# control_board.net
KiCad netlist of a schematic drawn in EAGLE
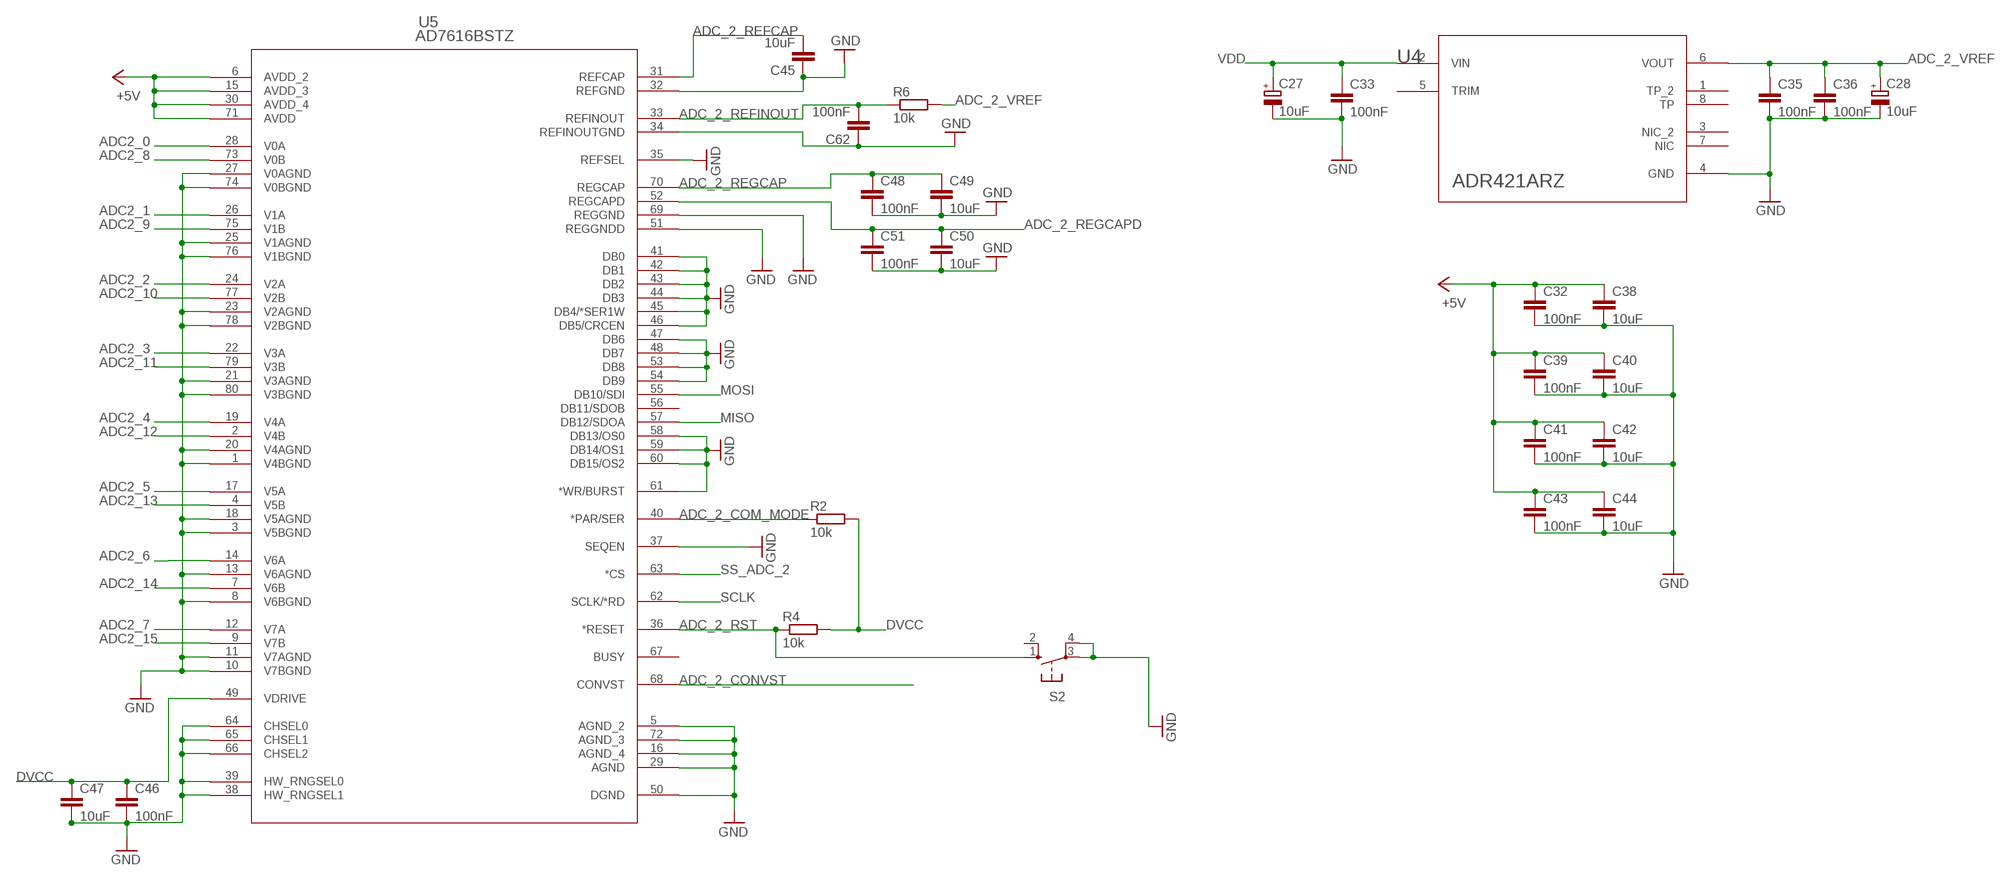
[diagram p0: schematic, sheet 1]
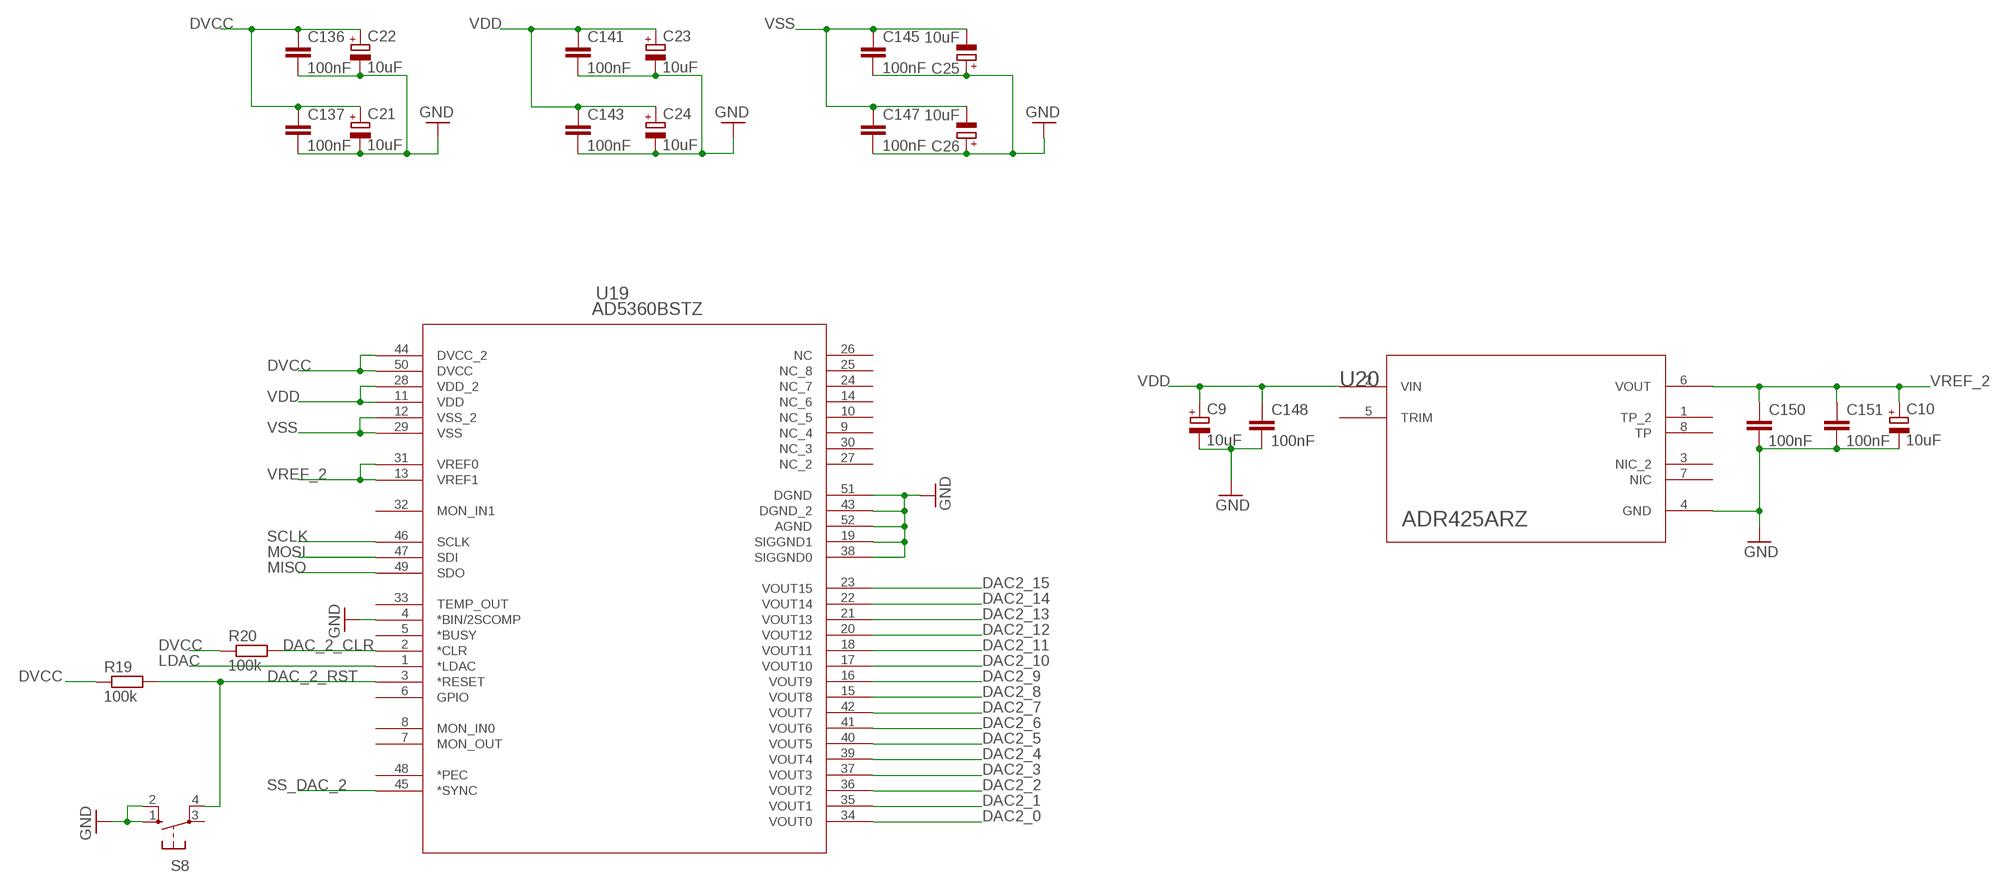
[diagram p1: schematic, sheet 2]
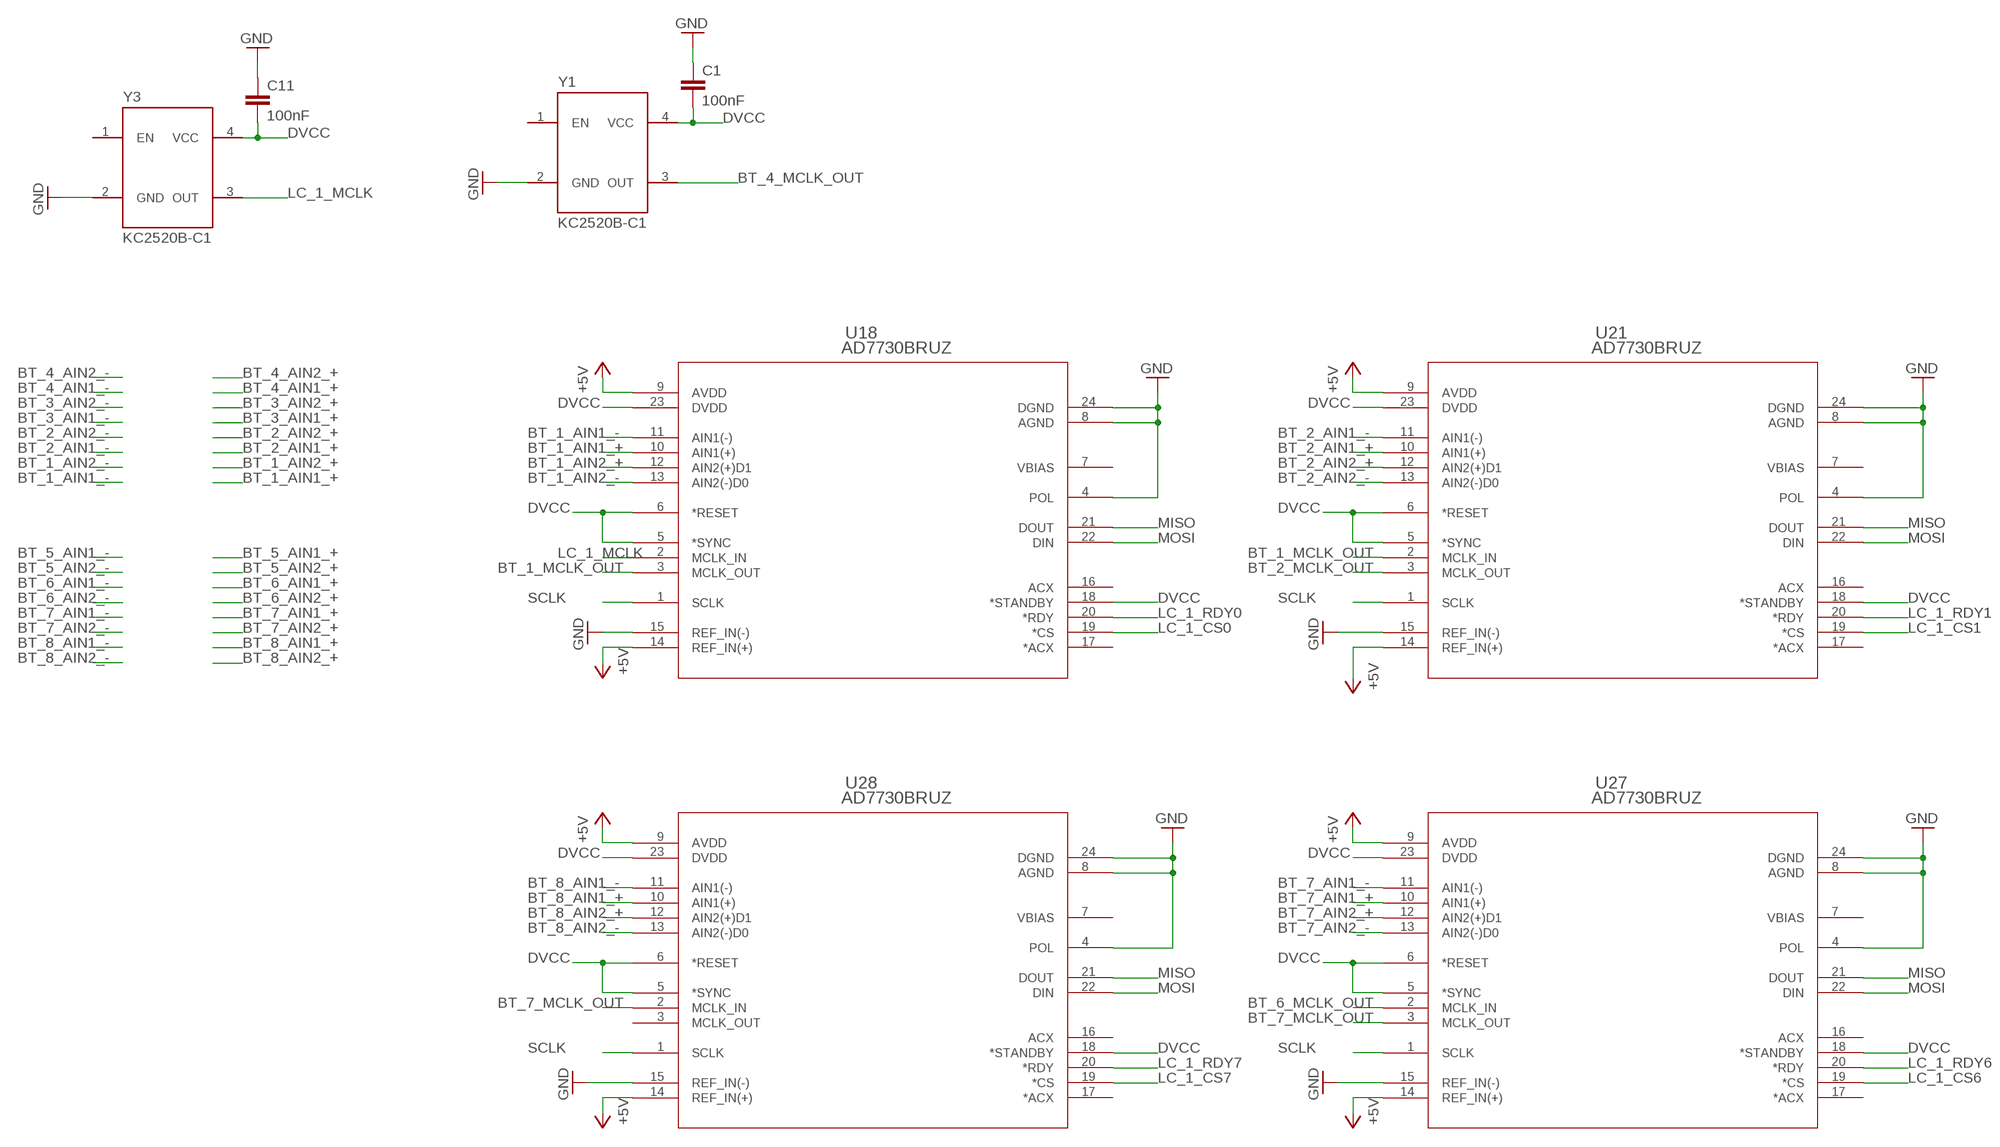
[diagram p2: schematic, sheet 3, part 1 of 2]
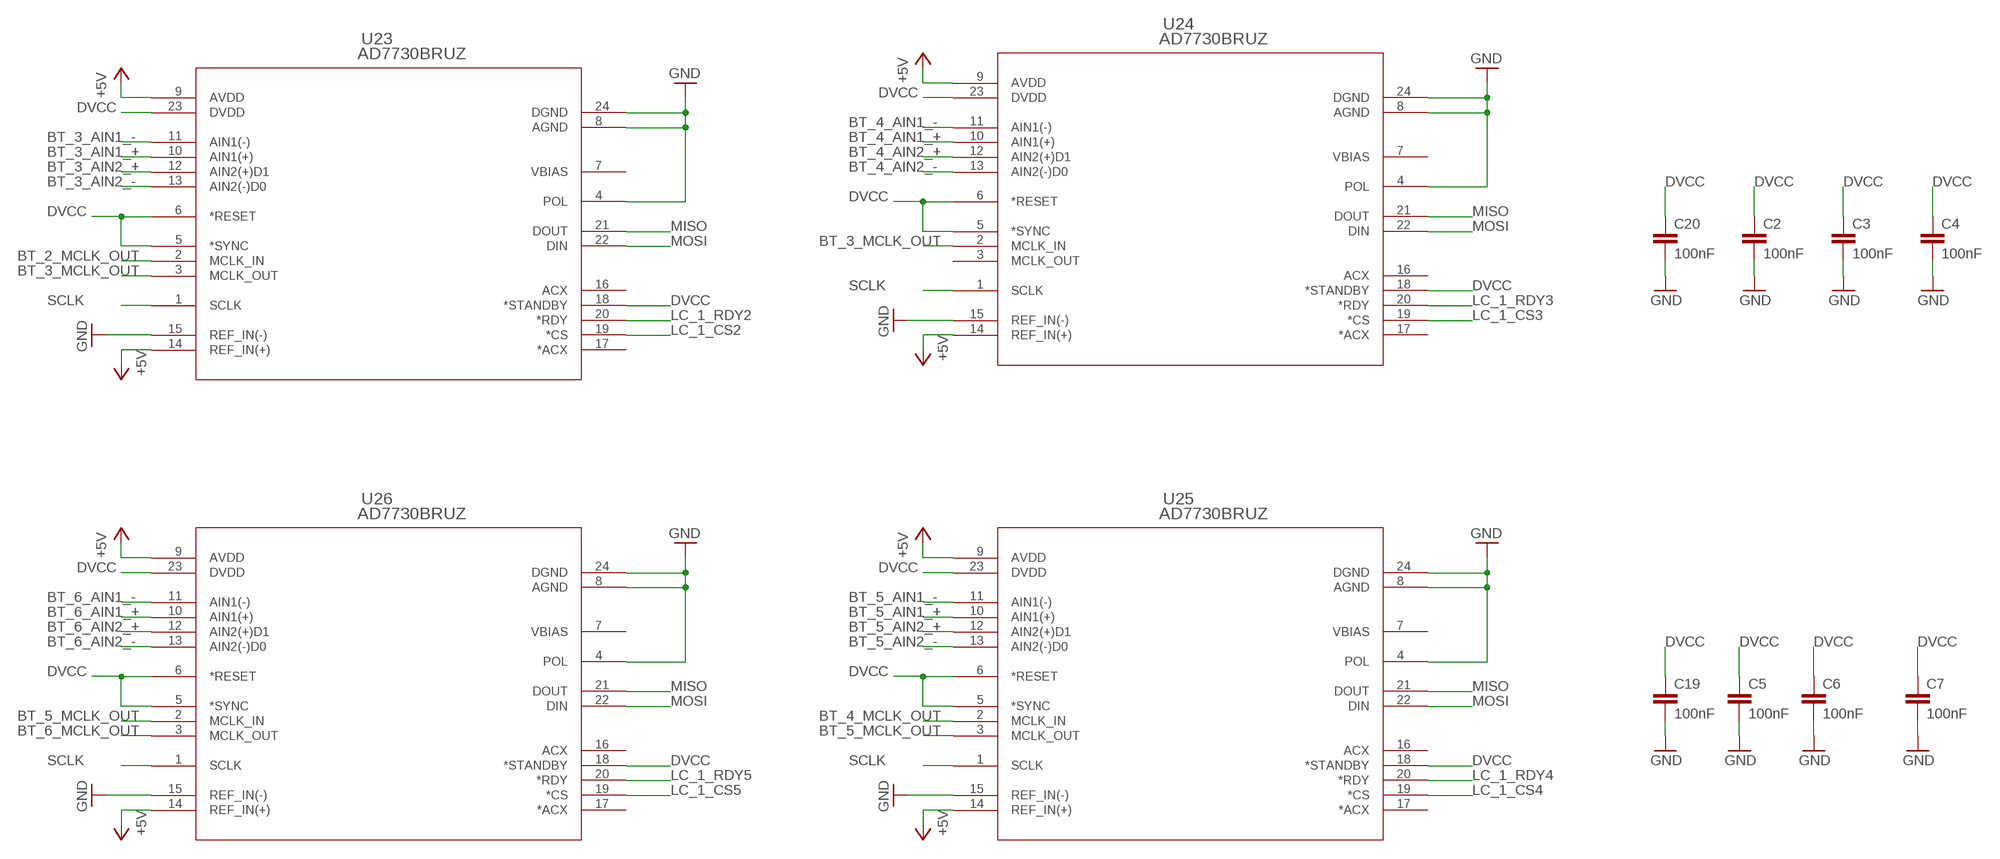
[diagram p3: schematic, sheet 3, part 2 of 2]
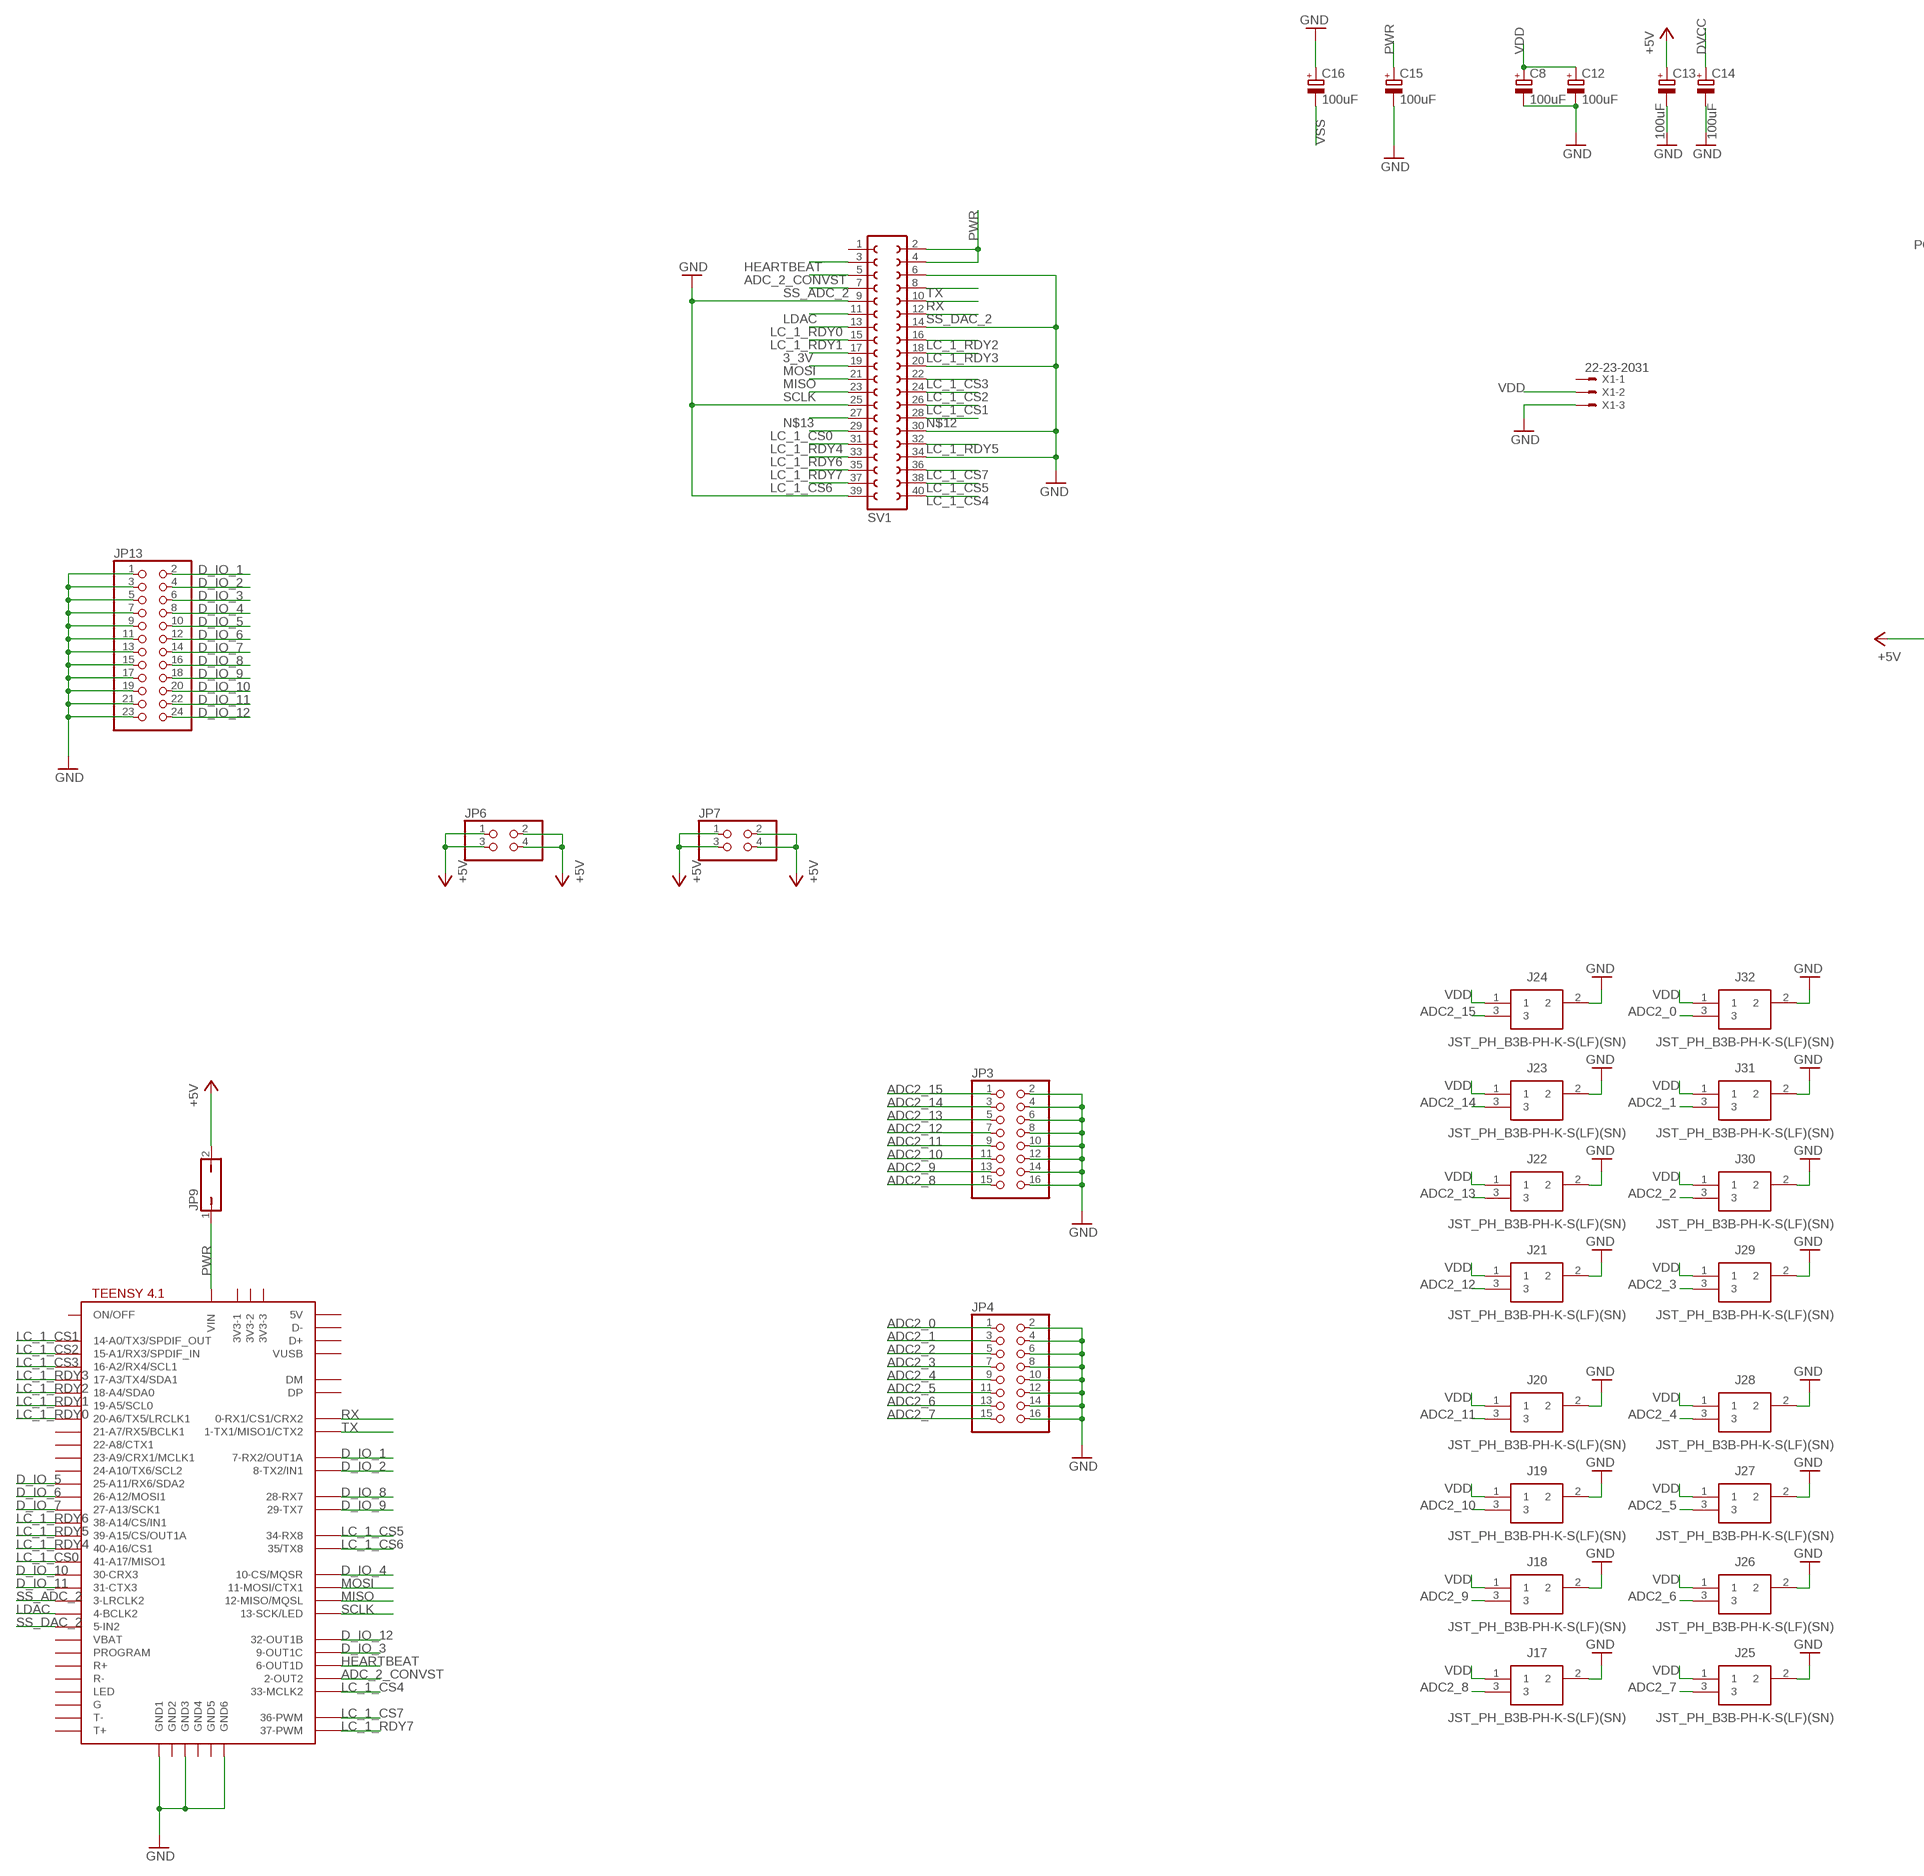
[diagram p4: schematic, sheet 4, part 1 of 2]
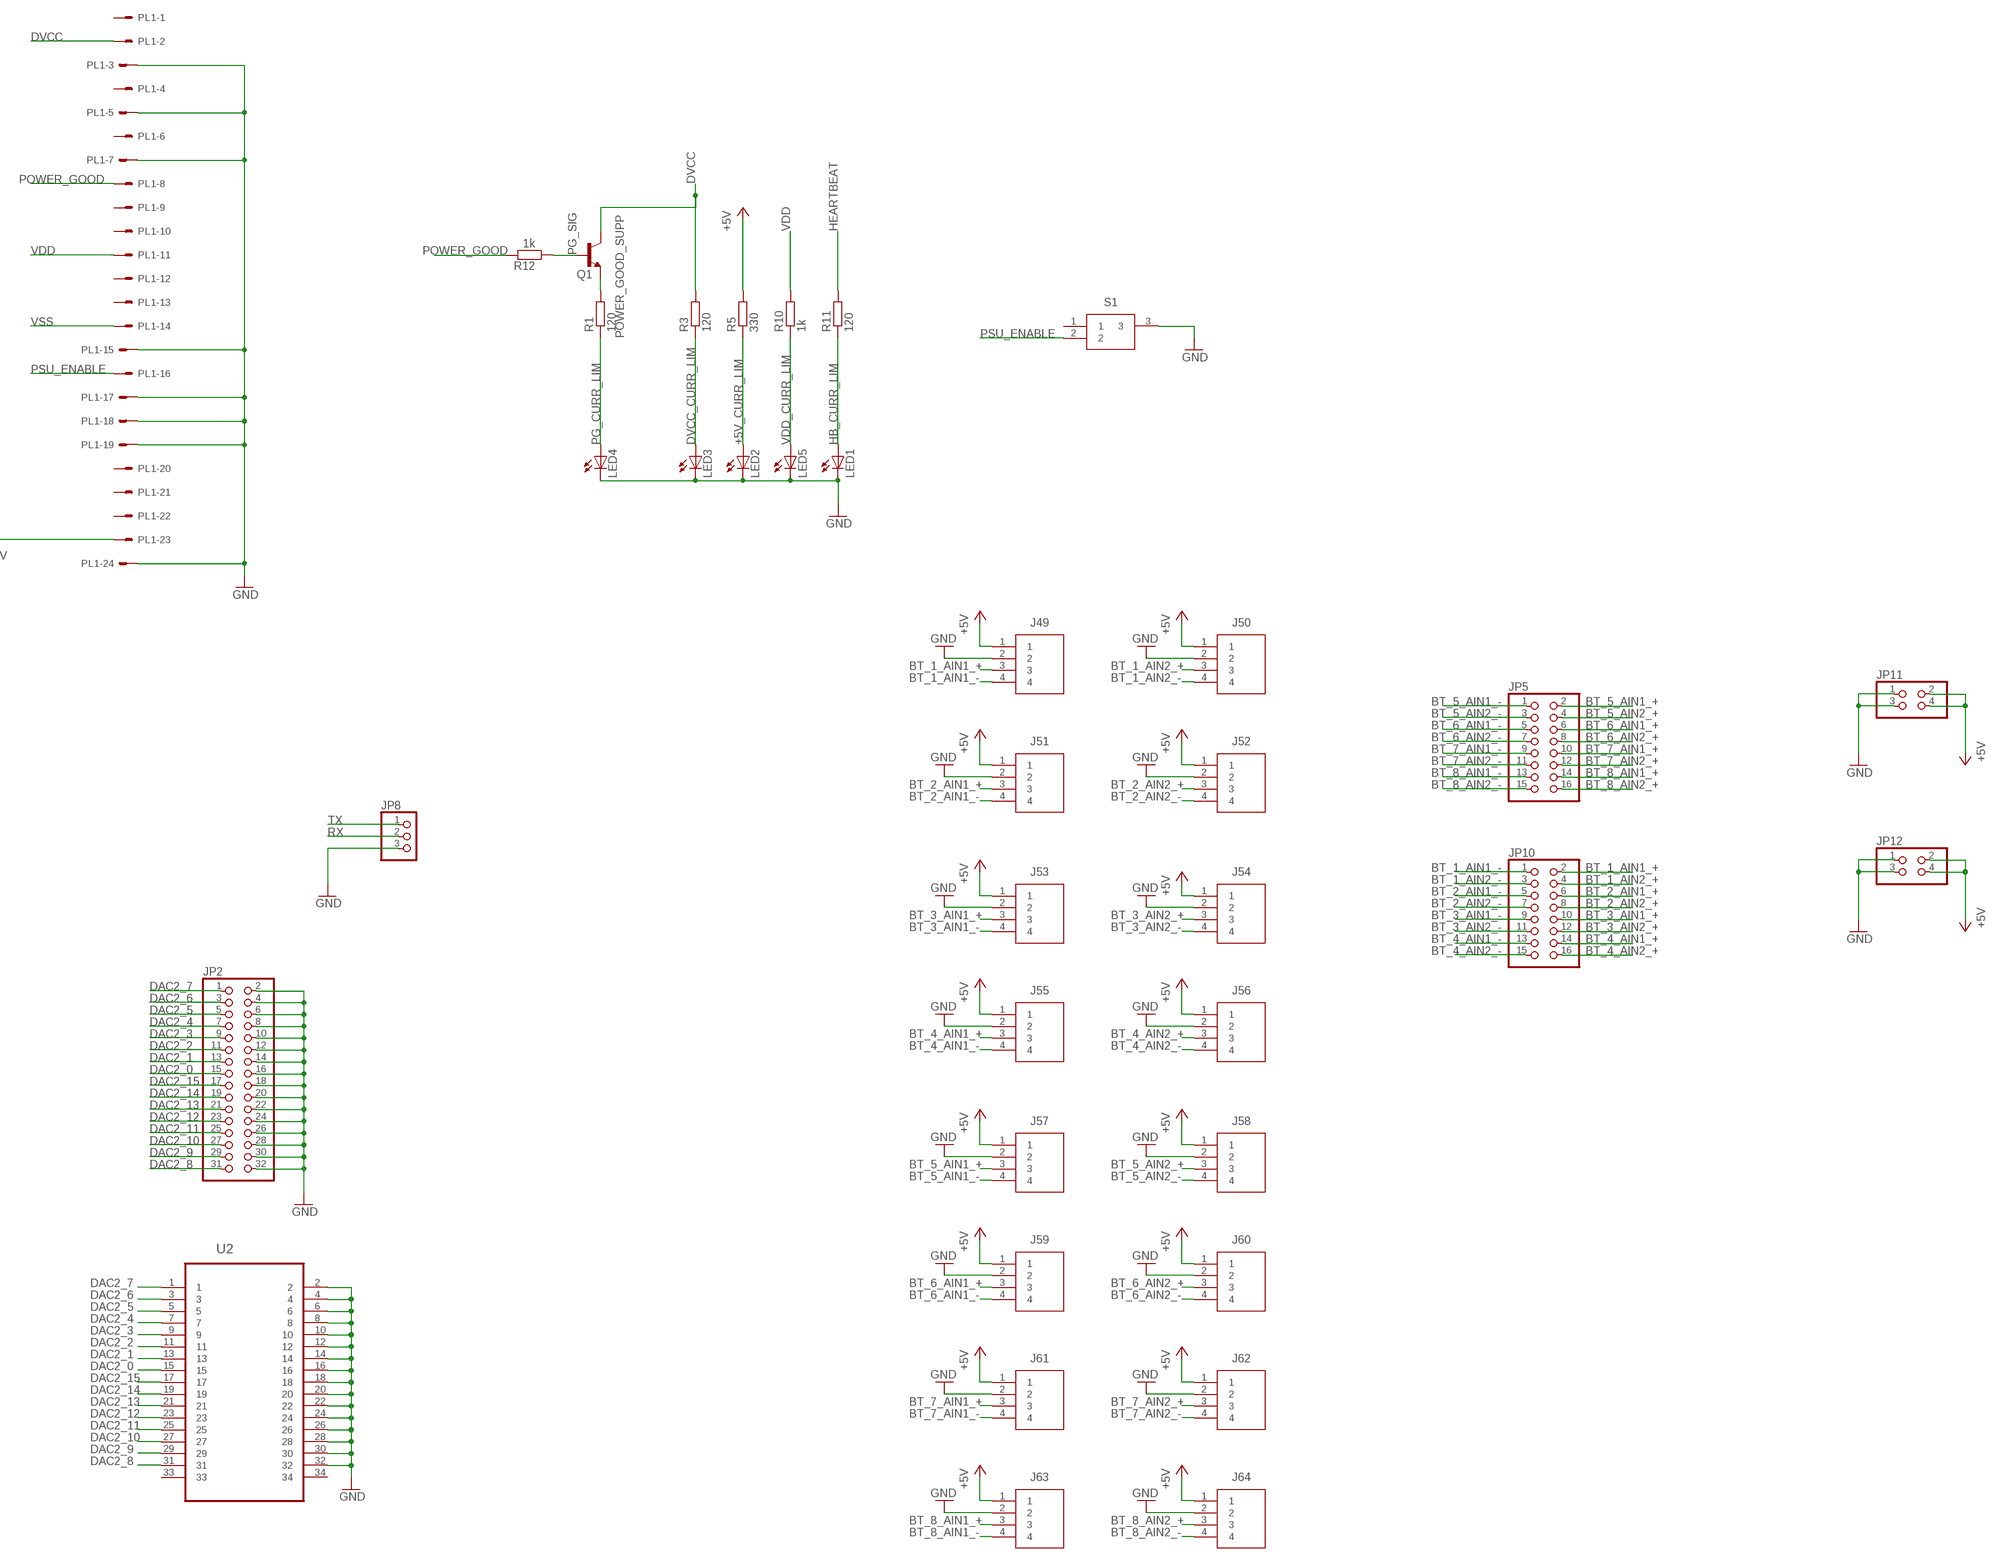
[diagram p5: schematic, sheet 4, part 2 of 2]

(export (version "E")
  (design (tool "Eeschema 10.0.6"))
  (components
    (comp (ref "C1")
      (value "100nF")
      (footprint "eagle-import:C0603")
      (libsource (lib "eagle-import") (part "C-EUC0603"))
    )
    (comp (ref "C2")
      (value "100nF")
      (footprint "eagle-import:C0603")
      (libsource (lib "eagle-import") (part "C-EUC0603"))
    )
    (comp (ref "C3")
      (value "100nF")
      (footprint "eagle-import:C0603")
      (libsource (lib "eagle-import") (part "C-EUC0603"))
    )
    (comp (ref "C4")
      (value "100nF")
      (footprint "eagle-import:C0603")
      (libsource (lib "eagle-import") (part "C-EUC0603"))
    )
    (comp (ref "C5")
      (value "100nF")
      (footprint "eagle-import:C0603")
      (libsource (lib "eagle-import") (part "C-EUC0603"))
    )
    (comp (ref "C6")
      (value "100nF")
      (footprint "eagle-import:C0603")
      (libsource (lib "eagle-import") (part "C-EUC0603"))
    )
    (comp (ref "C7")
      (value "100nF")
      (footprint "eagle-import:C0603")
      (libsource (lib "eagle-import") (part "C-EUC0603"))
    )
    (comp (ref "C11")
      (value "100nF")
      (footprint "eagle-import:C0603")
      (libsource (lib "eagle-import") (part "C-EUC0603"))
    )
    (comp (ref "C19")
      (value "100nF")
      (footprint "eagle-import:C0603")
      (libsource (lib "eagle-import") (part "C-EUC0603"))
    )
    (comp (ref "C20")
      (value "100nF")
      (footprint "eagle-import:C0603")
      (libsource (lib "eagle-import") (part "C-EUC0603"))
    )
    (comp (ref "U18")
      (value "AD7730BRUZ")
      (footprint "eagle-import:RU_24")
      (libsource (lib "eagle-import") (part "AD7730BRUZ"))
    )
    (comp (ref "U21")
      (value "AD7730BRUZ")
      (footprint "eagle-import:RU_24")
      (libsource (lib "eagle-import") (part "AD7730BRUZ"))
    )
    (comp (ref "U23")
      (value "AD7730BRUZ")
      (footprint "eagle-import:RU_24")
      (libsource (lib "eagle-import") (part "AD7730BRUZ"))
    )
    (comp (ref "U24")
      (value "AD7730BRUZ")
      (footprint "eagle-import:RU_24")
      (libsource (lib "eagle-import") (part "AD7730BRUZ"))
    )
    (comp (ref "U25")
      (value "AD7730BRUZ")
      (footprint "eagle-import:RU_24")
      (libsource (lib "eagle-import") (part "AD7730BRUZ"))
    )
    (comp (ref "U26")
      (value "AD7730BRUZ")
      (footprint "eagle-import:RU_24")
      (libsource (lib "eagle-import") (part "AD7730BRUZ"))
    )
    (comp (ref "U27")
      (value "AD7730BRUZ")
      (footprint "eagle-import:RU_24")
      (libsource (lib "eagle-import") (part "AD7730BRUZ"))
    )
    (comp (ref "U28")
      (value "AD7730BRUZ")
      (footprint "eagle-import:RU_24")
      (libsource (lib "eagle-import") (part "AD7730BRUZ"))
    )
    (comp (ref "Y1")
      (value "KC2520B-C1")
      (footprint "eagle-import:KC2520B-C1")
      (libsource (lib "eagle-import") (part "KC2520B-C1"))
    )
    (comp (ref "Y3")
      (value "KC2520B-C1")
      (footprint "eagle-import:KC2520B-C1")
      (libsource (lib "eagle-import") (part "KC2520B-C1"))
    )
    (comp (ref "C27")
      (value "10uF")
      (footprint "eagle-import:SMC_A")
      (libsource (lib "eagle-import") (part "resistor_348_CPOL-EUSMCA"))
    )
    (comp (ref "C28")
      (value "10uF")
      (footprint "eagle-import:SMC_A")
      (libsource (lib "eagle-import") (part "resistor_348_CPOL-EUSMCA"))
    )
    (comp (ref "C32")
      (value "100nF")
      (footprint "eagle-import:C0603")
      (libsource (lib "eagle-import") (part "C-EUC0603"))
    )
    (comp (ref "C33")
      (value "100nF")
      (footprint "eagle-import:C0603")
      (libsource (lib "eagle-import") (part "C-EUC0603"))
    )
    (comp (ref "C35")
      (value "100nF")
      (footprint "eagle-import:C0603")
      (libsource (lib "eagle-import") (part "C-EUC0603"))
    )
    (comp (ref "C36")
      (value "100nF")
      (footprint "eagle-import:C0603")
      (libsource (lib "eagle-import") (part "C-EUC0603"))
    )
    (comp (ref "C38")
      (value "10uF")
      (footprint "eagle-import:C0603")
      (libsource (lib "eagle-import") (part "C-EUC0603"))
    )
    (comp (ref "C39")
      (value "100nF")
      (footprint "eagle-import:C0603")
      (libsource (lib "eagle-import") (part "C-EUC0603"))
    )
    (comp (ref "C40")
      (value "10uF")
      (footprint "eagle-import:C0603")
      (libsource (lib "eagle-import") (part "C-EUC0603"))
    )
    (comp (ref "C41")
      (value "100nF")
      (footprint "eagle-import:C0603")
      (libsource (lib "eagle-import") (part "C-EUC0603"))
    )
    (comp (ref "C42")
      (value "10uF")
      (footprint "eagle-import:C0603")
      (libsource (lib "eagle-import") (part "C-EUC0603"))
    )
    (comp (ref "C43")
      (value "100nF")
      (footprint "eagle-import:C0603")
      (libsource (lib "eagle-import") (part "C-EUC0603"))
    )
    (comp (ref "C44")
      (value "10uF")
      (footprint "eagle-import:C0603")
      (libsource (lib "eagle-import") (part "C-EUC0603"))
    )
    (comp (ref "C45")
      (value "10uF")
      (footprint "eagle-import:C0603")
      (libsource (lib "eagle-import") (part "C-EUC0603"))
    )
    (comp (ref "C46")
      (value "100nF")
      (footprint "eagle-import:C0603")
      (libsource (lib "eagle-import") (part "C-EUC0603"))
    )
    (comp (ref "C47")
      (value "10uF")
      (footprint "eagle-import:C0603")
      (libsource (lib "eagle-import") (part "C-EUC0603"))
    )
    (comp (ref "C48")
      (value "100nF")
      (footprint "eagle-import:C0603")
      (libsource (lib "eagle-import") (part "C-EUC0603"))
    )
    (comp (ref "C49")
      (value "10uF")
      (footprint "eagle-import:C0603")
      (libsource (lib "eagle-import") (part "C-EUC0603"))
    )
    (comp (ref "C50")
      (value "10uF")
      (footprint "eagle-import:C0603")
      (libsource (lib "eagle-import") (part "C-EUC0603"))
    )
    (comp (ref "C51")
      (value "100nF")
      (footprint "eagle-import:C0603")
      (libsource (lib "eagle-import") (part "C-EUC0603"))
    )
    (comp (ref "C62")
      (value "100nF")
      (footprint "eagle-import:C0603")
      (libsource (lib "eagle-import") (part "C-EUC0603"))
    )
    (comp (ref "R2")
      (value "10k")
      (footprint "eagle-import:R0603")
      (libsource (lib "eagle-import") (part "R-EU_R0603"))
    )
    (comp (ref "R4")
      (value "10k")
      (footprint "eagle-import:R0603")
      (libsource (lib "eagle-import") (part "R-EU_R0603"))
    )
    (comp (ref "R6")
      (value "10k")
      (footprint "eagle-import:R0603")
      (libsource (lib "eagle-import") (part "R-EU_R0603"))
    )
    (comp (ref "S2")
      (value "10-XX")
      (footprint "eagle-import:B3F-10XX")
      (fields (field (name "MPN") "B3F-1000"))
      (libsource (lib "eagle-import") (part "10-XX"))
    )
    (comp (ref "U4")
      (value "ADR421ARZ")
      (footprint "eagle-import:R_8")
      (fields (field (name "MANUFACTURER_PART_NUMBER") "ADR423ARZ"))
      (libsource (lib "eagle-import") (part "ADR423ARZ"))
    )
    (comp (ref "U5")
      (value "AD7616BSTZ")
      (footprint "eagle-import:ST_80_2")
      (libsource (lib "eagle-import") (part "AD7616BSTZ"))
    )
    (comp (ref "C9")
      (value "10uF")
      (footprint "eagle-import:SMC_A")
      (libsource (lib "eagle-import") (part "resistor_348_CPOL-EUSMCA"))
    )
    (comp (ref "C10")
      (value "10uF")
      (footprint "eagle-import:SMC_A")
      (libsource (lib "eagle-import") (part "resistor_348_CPOL-EUSMCA"))
    )
    (comp (ref "C21")
      (value "10uF")
      (footprint "eagle-import:SMC_A")
      (libsource (lib "eagle-import") (part "resistor_348_CPOL-EUSMCA"))
    )
    (comp (ref "C22")
      (value "10uF")
      (footprint "eagle-import:SMC_A")
      (libsource (lib "eagle-import") (part "resistor_348_CPOL-EUSMCA"))
    )
    (comp (ref "C23")
      (value "10uF")
      (footprint "eagle-import:SMC_A")
      (libsource (lib "eagle-import") (part "resistor_348_CPOL-EUSMCA"))
    )
    (comp (ref "C24")
      (value "10uF")
      (footprint "eagle-import:SMC_A")
      (libsource (lib "eagle-import") (part "resistor_348_CPOL-EUSMCA"))
    )
    (comp (ref "C25")
      (value "10uF")
      (footprint "eagle-import:SMC_A")
      (libsource (lib "eagle-import") (part "resistor_348_CPOL-EUSMCA"))
    )
    (comp (ref "C26")
      (value "10uF")
      (footprint "eagle-import:SMC_A")
      (libsource (lib "eagle-import") (part "resistor_348_CPOL-EUSMCA"))
    )
    (comp (ref "C136")
      (value "100nF")
      (footprint "eagle-import:C0603")
      (libsource (lib "eagle-import") (part "C-EUC0603"))
    )
    (comp (ref "C137")
      (value "100nF")
      (footprint "eagle-import:C0603")
      (libsource (lib "eagle-import") (part "C-EUC0603"))
    )
    (comp (ref "C141")
      (value "100nF")
      (footprint "eagle-import:C0603")
      (libsource (lib "eagle-import") (part "C-EUC0603"))
    )
    (comp (ref "C143")
      (value "100nF")
      (footprint "eagle-import:C0603")
      (libsource (lib "eagle-import") (part "C-EUC0603"))
    )
    (comp (ref "C145")
      (value "100nF")
      (footprint "eagle-import:C0603")
      (libsource (lib "eagle-import") (part "C-EUC0603"))
    )
    (comp (ref "C147")
      (value "100nF")
      (footprint "eagle-import:C0603")
      (libsource (lib "eagle-import") (part "C-EUC0603"))
    )
    (comp (ref "C148")
      (value "100nF")
      (footprint "eagle-import:C0603")
      (libsource (lib "eagle-import") (part "C-EUC0603"))
    )
    (comp (ref "C150")
      (value "100nF")
      (footprint "eagle-import:C0603")
      (libsource (lib "eagle-import") (part "C-EUC0603"))
    )
    (comp (ref "C151")
      (value "100nF")
      (footprint "eagle-import:C0603")
      (libsource (lib "eagle-import") (part "C-EUC0603"))
    )
    (comp (ref "R19")
      (value "100k")
      (footprint "eagle-import:R0603")
      (libsource (lib "eagle-import") (part "R-EU_R0603"))
    )
    (comp (ref "R20")
      (value "100k")
      (footprint "eagle-import:R0603")
      (libsource (lib "eagle-import") (part "R-EU_R0603"))
    )
    (comp (ref "S8")
      (value "10-XX")
      (footprint "eagle-import:B3F-10XX")
      (fields (field (name "MPN") "B3F-1000"))
      (libsource (lib "eagle-import") (part "10-XX"))
    )
    (comp (ref "U19")
      (value "AD5360BSTZ")
      (footprint "eagle-import:ST_52")
      (libsource (lib "eagle-import") (part "AD5360BSTZ"))
    )
    (comp (ref "U20")
      (value "ADR425ARZ")
      (footprint "eagle-import:R_8")
      (fields (field (name "MANUFACTURER_PART_NUMBER") "ADR423ARZ"))
      (libsource (lib "eagle-import") (part "ADR423ARZ"))
    )
    (comp (ref "C8")
      (value "100uF")
      (footprint "eagle-import:E3,5-8")
      (libsource (lib "eagle-import") (part "CPOL-EUE3.5-8"))
    )
    (comp (ref "C12")
      (value "100uF")
      (footprint "eagle-import:E3,5-8")
      (libsource (lib "eagle-import") (part "CPOL-EUE3.5-8"))
    )
    (comp (ref "C13")
      (value "100uF")
      (footprint "eagle-import:E3,5-8")
      (libsource (lib "eagle-import") (part "CPOL-EUE3.5-8"))
    )
    (comp (ref "C14")
      (value "100uF")
      (footprint "eagle-import:E3,5-8")
      (libsource (lib "eagle-import") (part "CPOL-EUE3.5-8"))
    )
    (comp (ref "C15")
      (value "100uF")
      (footprint "eagle-import:E3,5-8")
      (libsource (lib "eagle-import") (part "CPOL-EUE3.5-8"))
    )
    (comp (ref "C16")
      (value "100uF")
      (footprint "eagle-import:E3,5-8")
      (libsource (lib "eagle-import") (part "CPOL-EUE3.5-8"))
    )
    (comp (ref "J17")
      (value "JST_PH_B3B-PH-K-S(LF)(SN)")
      (footprint "eagle-import:JST_PH_SHDR3W50P0X200_1X3_790X450X600")
      (fields
        (field (name "MANUFACTURER_PART_NUMBER") "B3B-PH-K-S(LF)(SN)")
        (field (name "RS_PART_NUMBER") "8201431P")
      )
      (libsource (lib "eagle-import") (part "JST_PH_B3B-PH-K-S(LF)(SN)"))
    )
    (comp (ref "J18")
      (value "JST_PH_B3B-PH-K-S(LF)(SN)")
      (footprint "eagle-import:JST_PH_SHDR3W50P0X200_1X3_790X450X600")
      (fields
        (field (name "MANUFACTURER_PART_NUMBER") "B3B-PH-K-S(LF)(SN)")
        (field (name "RS_PART_NUMBER") "8201431P")
      )
      (libsource (lib "eagle-import") (part "JST_PH_B3B-PH-K-S(LF)(SN)"))
    )
    (comp (ref "J19")
      (value "JST_PH_B3B-PH-K-S(LF)(SN)")
      (footprint "eagle-import:JST_PH_SHDR3W50P0X200_1X3_790X450X600")
      (fields
        (field (name "MANUFACTURER_PART_NUMBER") "B3B-PH-K-S(LF)(SN)")
        (field (name "RS_PART_NUMBER") "8201431P")
      )
      (libsource (lib "eagle-import") (part "JST_PH_B3B-PH-K-S(LF)(SN)"))
    )
    (comp (ref "J20")
      (value "JST_PH_B3B-PH-K-S(LF)(SN)")
      (footprint "eagle-import:JST_PH_SHDR3W50P0X200_1X3_790X450X600")
      (fields
        (field (name "MANUFACTURER_PART_NUMBER") "B3B-PH-K-S(LF)(SN)")
        (field (name "RS_PART_NUMBER") "8201431P")
      )
      (libsource (lib "eagle-import") (part "JST_PH_B3B-PH-K-S(LF)(SN)"))
    )
    (comp (ref "J21")
      (value "JST_PH_B3B-PH-K-S(LF)(SN)")
      (footprint "eagle-import:JST_PH_SHDR3W50P0X200_1X3_790X450X600")
      (fields
        (field (name "MANUFACTURER_PART_NUMBER") "B3B-PH-K-S(LF)(SN)")
        (field (name "RS_PART_NUMBER") "8201431P")
      )
      (libsource (lib "eagle-import") (part "JST_PH_B3B-PH-K-S(LF)(SN)"))
    )
    (comp (ref "J22")
      (value "JST_PH_B3B-PH-K-S(LF)(SN)")
      (footprint "eagle-import:JST_PH_SHDR3W50P0X200_1X3_790X450X600")
      (fields
        (field (name "MANUFACTURER_PART_NUMBER") "B3B-PH-K-S(LF)(SN)")
        (field (name "RS_PART_NUMBER") "8201431P")
      )
      (libsource (lib "eagle-import") (part "JST_PH_B3B-PH-K-S(LF)(SN)"))
    )
    (comp (ref "J23")
      (value "JST_PH_B3B-PH-K-S(LF)(SN)")
      (footprint "eagle-import:JST_PH_SHDR3W50P0X200_1X3_790X450X600")
      (fields
        (field (name "MANUFACTURER_PART_NUMBER") "B3B-PH-K-S(LF)(SN)")
        (field (name "RS_PART_NUMBER") "8201431P")
      )
      (libsource (lib "eagle-import") (part "JST_PH_B3B-PH-K-S(LF)(SN)"))
    )
    (comp (ref "J24")
      (value "JST_PH_B3B-PH-K-S(LF)(SN)")
      (footprint "eagle-import:JST_PH_SHDR3W50P0X200_1X3_790X450X600")
      (fields
        (field (name "MANUFACTURER_PART_NUMBER") "B3B-PH-K-S(LF)(SN)")
        (field (name "RS_PART_NUMBER") "8201431P")
      )
      (libsource (lib "eagle-import") (part "JST_PH_B3B-PH-K-S(LF)(SN)"))
    )
    (comp (ref "J25")
      (value "JST_PH_B3B-PH-K-S(LF)(SN)")
      (footprint "eagle-import:JST_PH_SHDR3W50P0X200_1X3_790X450X600")
      (fields
        (field (name "MANUFACTURER_PART_NUMBER") "B3B-PH-K-S(LF)(SN)")
        (field (name "RS_PART_NUMBER") "8201431P")
      )
      (libsource (lib "eagle-import") (part "JST_PH_B3B-PH-K-S(LF)(SN)"))
    )
    (comp (ref "J26")
      (value "JST_PH_B3B-PH-K-S(LF)(SN)")
      (footprint "eagle-import:JST_PH_SHDR3W50P0X200_1X3_790X450X600")
      (fields
        (field (name "MANUFACTURER_PART_NUMBER") "B3B-PH-K-S(LF)(SN)")
        (field (name "RS_PART_NUMBER") "8201431P")
      )
      (libsource (lib "eagle-import") (part "JST_PH_B3B-PH-K-S(LF)(SN)"))
    )
    (comp (ref "J27")
      (value "JST_PH_B3B-PH-K-S(LF)(SN)")
      (footprint "eagle-import:JST_PH_SHDR3W50P0X200_1X3_790X450X600")
      (fields
        (field (name "MANUFACTURER_PART_NUMBER") "B3B-PH-K-S(LF)(SN)")
        (field (name "RS_PART_NUMBER") "8201431P")
      )
      (libsource (lib "eagle-import") (part "JST_PH_B3B-PH-K-S(LF)(SN)"))
    )
    (comp (ref "J28")
      (value "JST_PH_B3B-PH-K-S(LF)(SN)")
      (footprint "eagle-import:JST_PH_SHDR3W50P0X200_1X3_790X450X600")
      (fields
        (field (name "MANUFACTURER_PART_NUMBER") "B3B-PH-K-S(LF)(SN)")
        (field (name "RS_PART_NUMBER") "8201431P")
      )
      (libsource (lib "eagle-import") (part "JST_PH_B3B-PH-K-S(LF)(SN)"))
    )
    (comp (ref "J29")
      (value "JST_PH_B3B-PH-K-S(LF)(SN)")
      (footprint "eagle-import:JST_PH_SHDR3W50P0X200_1X3_790X450X600")
      (fields
        (field (name "MANUFACTURER_PART_NUMBER") "B3B-PH-K-S(LF)(SN)")
        (field (name "RS_PART_NUMBER") "8201431P")
      )
      (libsource (lib "eagle-import") (part "JST_PH_B3B-PH-K-S(LF)(SN)"))
    )
    (comp (ref "J30")
      (value "JST_PH_B3B-PH-K-S(LF)(SN)")
      (footprint "eagle-import:JST_PH_SHDR3W50P0X200_1X3_790X450X600")
      (fields
        (field (name "MANUFACTURER_PART_NUMBER") "B3B-PH-K-S(LF)(SN)")
        (field (name "RS_PART_NUMBER") "8201431P")
      )
      (libsource (lib "eagle-import") (part "JST_PH_B3B-PH-K-S(LF)(SN)"))
    )
    (comp (ref "J31")
      (value "JST_PH_B3B-PH-K-S(LF)(SN)")
      (footprint "eagle-import:JST_PH_SHDR3W50P0X200_1X3_790X450X600")
      (fields
        (field (name "MANUFACTURER_PART_NUMBER") "B3B-PH-K-S(LF)(SN)")
        (field (name "RS_PART_NUMBER") "8201431P")
      )
      (libsource (lib "eagle-import") (part "JST_PH_B3B-PH-K-S(LF)(SN)"))
    )
    (comp (ref "J32")
      (value "JST_PH_B3B-PH-K-S(LF)(SN)")
      (footprint "eagle-import:JST_PH_SHDR3W50P0X200_1X3_790X450X600")
      (fields
        (field (name "MANUFACTURER_PART_NUMBER") "B3B-PH-K-S(LF)(SN)")
        (field (name "RS_PART_NUMBER") "8201431P")
      )
      (libsource (lib "eagle-import") (part "JST_PH_B3B-PH-K-S(LF)(SN)"))
    )
    (comp (ref "J49")
      (value "B4B-PH-K-S(LF)(SN)")
      (footprint "eagle-import:SHDR4W50P0X200_1X4_990X450X600")
      (fields (field (name "RS_PART_NUMBER") "8201434P"))
      (libsource (lib "eagle-import") (part "B4B-PH-K-S(LF)(SN)"))
    )
    (comp (ref "J50")
      (value "B4B-PH-K-S(LF)(SN)")
      (footprint "eagle-import:SHDR4W50P0X200_1X4_990X450X600")
      (fields (field (name "RS_PART_NUMBER") "8201434P"))
      (libsource (lib "eagle-import") (part "B4B-PH-K-S(LF)(SN)"))
    )
    (comp (ref "J51")
      (value "B4B-PH-K-S(LF)(SN)")
      (footprint "eagle-import:SHDR4W50P0X200_1X4_990X450X600")
      (fields (field (name "RS_PART_NUMBER") "8201434P"))
      (libsource (lib "eagle-import") (part "B4B-PH-K-S(LF)(SN)"))
    )
    (comp (ref "J52")
      (value "B4B-PH-K-S(LF)(SN)")
      (footprint "eagle-import:SHDR4W50P0X200_1X4_990X450X600")
      (fields (field (name "RS_PART_NUMBER") "8201434P"))
      (libsource (lib "eagle-import") (part "B4B-PH-K-S(LF)(SN)"))
    )
    (comp (ref "J53")
      (value "B4B-PH-K-S(LF)(SN)")
      (footprint "eagle-import:SHDR4W50P0X200_1X4_990X450X600")
      (fields (field (name "RS_PART_NUMBER") "8201434P"))
      (libsource (lib "eagle-import") (part "B4B-PH-K-S(LF)(SN)"))
    )
    (comp (ref "J54")
      (value "B4B-PH-K-S(LF)(SN)")
      (footprint "eagle-import:SHDR4W50P0X200_1X4_990X450X600")
      (fields (field (name "RS_PART_NUMBER") "8201434P"))
      (libsource (lib "eagle-import") (part "B4B-PH-K-S(LF)(SN)"))
    )
    (comp (ref "J55")
      (value "B4B-PH-K-S(LF)(SN)")
      (footprint "eagle-import:SHDR4W50P0X200_1X4_990X450X600")
      (fields (field (name "RS_PART_NUMBER") "8201434P"))
      (libsource (lib "eagle-import") (part "B4B-PH-K-S(LF)(SN)"))
    )
    (comp (ref "J56")
      (value "B4B-PH-K-S(LF)(SN)")
      (footprint "eagle-import:SHDR4W50P0X200_1X4_990X450X600")
      (fields (field (name "RS_PART_NUMBER") "8201434P"))
      (libsource (lib "eagle-import") (part "B4B-PH-K-S(LF)(SN)"))
    )
    (comp (ref "J57")
      (value "B4B-PH-K-S(LF)(SN)")
      (footprint "eagle-import:SHDR4W50P0X200_1X4_990X450X600")
      (fields (field (name "RS_PART_NUMBER") "8201434P"))
      (libsource (lib "eagle-import") (part "B4B-PH-K-S(LF)(SN)"))
    )
    (comp (ref "J58")
      (value "B4B-PH-K-S(LF)(SN)")
      (footprint "eagle-import:SHDR4W50P0X200_1X4_990X450X600")
      (fields (field (name "RS_PART_NUMBER") "8201434P"))
      (libsource (lib "eagle-import") (part "B4B-PH-K-S(LF)(SN)"))
    )
    (comp (ref "J59")
      (value "B4B-PH-K-S(LF)(SN)")
      (footprint "eagle-import:SHDR4W50P0X200_1X4_990X450X600")
      (fields (field (name "RS_PART_NUMBER") "8201434P"))
      (libsource (lib "eagle-import") (part "B4B-PH-K-S(LF)(SN)"))
    )
    (comp (ref "J60")
      (value "B4B-PH-K-S(LF)(SN)")
      (footprint "eagle-import:SHDR4W50P0X200_1X4_990X450X600")
      (fields (field (name "RS_PART_NUMBER") "8201434P"))
      (libsource (lib "eagle-import") (part "B4B-PH-K-S(LF)(SN)"))
    )
    (comp (ref "J61")
      (value "B4B-PH-K-S(LF)(SN)")
      (footprint "eagle-import:SHDR4W50P0X200_1X4_990X450X600")
      (fields (field (name "RS_PART_NUMBER") "8201434P"))
      (libsource (lib "eagle-import") (part "B4B-PH-K-S(LF)(SN)"))
    )
    (comp (ref "J62")
      (value "B4B-PH-K-S(LF)(SN)")
      (footprint "eagle-import:SHDR4W50P0X200_1X4_990X450X600")
      (fields (field (name "RS_PART_NUMBER") "8201434P"))
      (libsource (lib "eagle-import") (part "B4B-PH-K-S(LF)(SN)"))
    )
    (comp (ref "J63")
      (value "B4B-PH-K-S(LF)(SN)")
      (footprint "eagle-import:SHDR4W50P0X200_1X4_990X450X600")
      (fields (field (name "RS_PART_NUMBER") "8201434P"))
      (libsource (lib "eagle-import") (part "B4B-PH-K-S(LF)(SN)"))
    )
    (comp (ref "J64")
      (value "B4B-PH-K-S(LF)(SN)")
      (footprint "eagle-import:SHDR4W50P0X200_1X4_990X450X600")
      (fields (field (name "RS_PART_NUMBER") "8201434P"))
      (libsource (lib "eagle-import") (part "B4B-PH-K-S(LF)(SN)"))
    )
    (comp (ref "JP2")
      (value "PINHD-2X16/90")
      (footprint "eagle-import:2X16_90")
      (libsource (lib "eagle-import") (part "PINHD-2X16/90"))
    )
    (comp (ref "JP3")
      (value "PINHD-2X8/90")
      (footprint "eagle-import:2X08_90")
      (libsource (lib "eagle-import") (part "PINHD-2X8/90"))
    )
    (comp (ref "JP4")
      (value "PINHD-2X8/90")
      (footprint "eagle-import:2X08_90")
      (libsource (lib "eagle-import") (part "PINHD-2X8/90"))
    )
    (comp (ref "JP5")
      (value "PINHD-2X8")
      (footprint "eagle-import:2X08")
      (libsource (lib "eagle-import") (part "PINHD-2X8"))
    )
    (comp (ref "JP6")
      (value "PINHD-2X2/90")
      (footprint "eagle-import:2X02_90")
      (libsource (lib "eagle-import") (part "PINHD-2X2/90"))
    )
    (comp (ref "JP7")
      (value "PINHD-2X2/90")
      (footprint "eagle-import:2X02_90")
      (libsource (lib "eagle-import") (part "PINHD-2X2/90"))
    )
    (comp (ref "JP8")
      (value "PINHD-1X3")
      (footprint "eagle-import:1X03")
      (libsource (lib "eagle-import") (part "PINHD-1X3"))
    )
    (comp (ref "JP9")
      (value "JP1Q")
      (footprint "eagle-import:JP1")
      (libsource (lib "eagle-import") (part "JP1Q"))
    )
    (comp (ref "JP10")
      (value "PINHD-2X8")
      (footprint "eagle-import:2X08")
      (libsource (lib "eagle-import") (part "PINHD-2X8"))
    )
    (comp (ref "JP11")
      (value "PINHD-2X2")
      (footprint "eagle-import:2X02")
      (libsource (lib "eagle-import") (part "PINHD-2X2"))
    )
    (comp (ref "JP12")
      (value "PINHD-2X2")
      (footprint "eagle-import:2X02")
      (libsource (lib "eagle-import") (part "PINHD-2X2"))
    )
    (comp (ref "JP13")
      (value "PINHD-2X12_2.54-SMD")
      (footprint "eagle-import:2X12SMD")
      (libsource (lib "eagle-import") (part "PINHD-2X12_2.54-SMD"))
    )
    (comp (ref "LED1")
      (value "LEDCHIP-LED0603")
      (footprint "eagle-import:CHIP-LED0603")
      (libsource (lib "eagle-import") (part "LEDCHIP-LED0603"))
    )
    (comp (ref "LED2")
      (value "LEDCHIP-LED0603")
      (footprint "eagle-import:CHIP-LED0603")
      (libsource (lib "eagle-import") (part "LEDCHIP-LED0603"))
    )
    (comp (ref "LED3")
      (value "LEDCHIP-LED0603")
      (footprint "eagle-import:CHIP-LED0603")
      (libsource (lib "eagle-import") (part "LEDCHIP-LED0603"))
    )
    (comp (ref "LED4")
      (value "LEDCHIP-LED0603")
      (footprint "eagle-import:CHIP-LED0603")
      (libsource (lib "eagle-import") (part "LEDCHIP-LED0603"))
    )
    (comp (ref "LED5")
      (value "LEDCHIP-LED0603")
      (footprint "eagle-import:CHIP-LED0603")
      (libsource (lib "eagle-import") (part "LEDCHIP-LED0603"))
    )
    (comp (ref "PL1")
      (value "555X-24V")
      (footprint "eagle-import:5566-24")
      (libsource (lib "eagle-import") (part "555X-24V"))
    )
    (comp (ref "Q1")
      (value "BCF29SMD")
      (footprint "eagle-import:SOT23-BEC")
      (libsource (lib "eagle-import") (part "BCF29SMD"))
    )
    (comp (ref "R1")
      (value "120")
      (footprint "eagle-import:R0805")
      (libsource (lib "eagle-import") (part "resistor_348_R-EU_R0805"))
    )
    (comp (ref "R3")
      (value "120")
      (footprint "eagle-import:R0805")
      (libsource (lib "eagle-import") (part "resistor_348_R-EU_R0805"))
    )
    (comp (ref "R5")
      (value "330")
      (footprint "eagle-import:R0805")
      (libsource (lib "eagle-import") (part "resistor_348_R-EU_R0805"))
    )
    (comp (ref "R10")
      (value "1k")
      (footprint "eagle-import:R0805")
      (libsource (lib "eagle-import") (part "resistor_348_R-EU_R0805"))
    )
    (comp (ref "R11")
      (value "120")
      (footprint "eagle-import:R0805")
      (libsource (lib "eagle-import") (part "resistor_348_R-EU_R0805"))
    )
    (comp (ref "R12")
      (value "1k")
      (footprint "eagle-import:R0805")
      (libsource (lib "eagle-import") (part "resistor_348_R-EU_R0805"))
    )
    (comp (ref "S1")
      (value "1MS1T1B1M2QES-5")
      (footprint "eagle-import:1MS1T1B1M2QES-5")
      (fields (field (name "RS_PART_NUMBER") "7347066P"))
      (libsource (lib "eagle-import") (part "1MS1T1B1M2QES-5"))
    )
    (comp (ref "SV1")
      (value "FE20-2")
      (footprint "eagle-import:FE20-2")
      (libsource (lib "eagle-import") (part "FE20-2"))
    )
    (comp (ref "U$1")
      (value "TEENSY41")
      (footprint "eagle-import:TEENSY41")
      (libsource (lib "eagle-import") (part "TEENSY41"))
    )
    (comp (ref "U2")
      (value "AMP-5103309-7-34PIN_5103309-7")
      (footprint "eagle-import:AMP-5103309-7-34PIN_TYCO_5103309-7")
      (fields (field (name "MPN") "5103309-7"))
      (libsource (lib "eagle-import") (part "AMP-5103309-7-34PIN_5103309-7"))
    )
    (comp (ref "X1")
      (value "22-23-2031")
      (footprint "eagle-import:22-23-2031")
      (fields (field (name "MF") "MOLEX"))
      (libsource (lib "eagle-import") (part "22-23-2031"))
    )
  )
  (nets
    (net (code "1") (name "+5V") (class "Default")
      (node (ref "C13") (pin "+") (pinfunction "+_+") (pintype "passive"))
      (node (ref "C32") (pin "1") (pinfunction "1_1") (pintype "passive"))
      (node (ref "C38") (pin "1") (pinfunction "1_1") (pintype "passive"))
      (node (ref "C39") (pin "1") (pinfunction "1_1") (pintype "passive"))
      (node (ref "C40") (pin "1") (pinfunction "1_1") (pintype "passive"))
      (node (ref "C41") (pin "1") (pinfunction "1_1") (pintype "passive"))
      (node (ref "C42") (pin "1") (pinfunction "1_1") (pintype "passive"))
      (node (ref "C43") (pin "1") (pinfunction "1_1") (pintype "passive"))
      (node (ref "C44") (pin "1") (pinfunction "1_1") (pintype "passive"))
      (node (ref "J49") (pin "1") (pinfunction "1_1") (pintype "passive"))
      (node (ref "J50") (pin "1") (pinfunction "1_1") (pintype "passive"))
      (node (ref "J51") (pin "1") (pinfunction "1_1") (pintype "passive"))
      (node (ref "J52") (pin "1") (pinfunction "1_1") (pintype "passive"))
      (node (ref "J53") (pin "1") (pinfunction "1_1") (pintype "passive"))
      (node (ref "J54") (pin "1") (pinfunction "1_1") (pintype "passive"))
      (node (ref "J55") (pin "1") (pinfunction "1_1") (pintype "passive"))
      (node (ref "J56") (pin "1") (pinfunction "1_1") (pintype "passive"))
      (node (ref "J57") (pin "1") (pinfunction "1_1") (pintype "passive"))
      (node (ref "J58") (pin "1") (pinfunction "1_1") (pintype "passive"))
      (node (ref "J59") (pin "1") (pinfunction "1_1") (pintype "passive"))
      (node (ref "J60") (pin "1") (pinfunction "1_1") (pintype "passive"))
      (node (ref "J61") (pin "1") (pinfunction "1_1") (pintype "passive"))
      (node (ref "J62") (pin "1") (pinfunction "1_1") (pintype "passive"))
      (node (ref "J63") (pin "1") (pinfunction "1_1") (pintype "passive"))
      (node (ref "J64") (pin "1") (pinfunction "1_1") (pintype "passive"))
      (node (ref "JP11") (pin "2") (pinfunction "2_2") (pintype "passive"))
      (node (ref "JP11") (pin "4") (pinfunction "4_4") (pintype "passive"))
      (node (ref "JP12") (pin "2") (pinfunction "2_2") (pintype "passive"))
      (node (ref "JP12") (pin "4") (pinfunction "4_4") (pintype "passive"))
      (node (ref "JP6") (pin "1") (pinfunction "1_1") (pintype "passive"))
      (node (ref "JP6") (pin "2") (pinfunction "2_2") (pintype "passive"))
      (node (ref "JP6") (pin "3") (pinfunction "3_3") (pintype "passive"))
      (node (ref "JP6") (pin "4") (pinfunction "4_4") (pintype "passive"))
      (node (ref "JP7") (pin "1") (pinfunction "1_1") (pintype "passive"))
      (node (ref "JP7") (pin "2") (pinfunction "2_2") (pintype "passive"))
      (node (ref "JP7") (pin "3") (pinfunction "3_3") (pintype "passive"))
      (node (ref "JP7") (pin "4") (pinfunction "4_4") (pintype "passive"))
      (node (ref "JP9") (pin "2") (pinfunction "2_2") (pintype "passive"))
      (node (ref "PL1") (pin "23") (pinfunction "S_23") (pintype "passive"))
      (node (ref "R5") (pin "2") (pinfunction "2_2") (pintype "passive"))
      (node (ref "U18") (pin "14") (pinfunction "REF_IN(+)_14") (pintype "passive"))
      (node (ref "U18") (pin "9") (pinfunction "AVDD_9") (pintype "passive"))
      (node (ref "U21") (pin "14") (pinfunction "REF_IN(+)_14") (pintype "passive"))
      (node (ref "U21") (pin "9") (pinfunction "AVDD_9") (pintype "passive"))
      (node (ref "U23") (pin "14") (pinfunction "REF_IN(+)_14") (pintype "passive"))
      (node (ref "U23") (pin "9") (pinfunction "AVDD_9") (pintype "passive"))
      (node (ref "U24") (pin "14") (pinfunction "REF_IN(+)_14") (pintype "passive"))
      (node (ref "U24") (pin "9") (pinfunction "AVDD_9") (pintype "passive"))
      (node (ref "U25") (pin "14") (pinfunction "REF_IN(+)_14") (pintype "passive"))
      (node (ref "U25") (pin "9") (pinfunction "AVDD_9") (pintype "passive"))
      (node (ref "U26") (pin "14") (pinfunction "REF_IN(+)_14") (pintype "passive"))
      (node (ref "U26") (pin "9") (pinfunction "AVDD_9") (pintype "passive"))
      (node (ref "U27") (pin "14") (pinfunction "REF_IN(+)_14") (pintype "passive"))
      (node (ref "U27") (pin "9") (pinfunction "AVDD_9") (pintype "passive"))
      (node (ref "U28") (pin "14") (pinfunction "REF_IN(+)_14") (pintype "passive"))
      (node (ref "U28") (pin "9") (pinfunction "AVDD_9") (pintype "passive"))
      (node (ref "U5") (pin "15") (pinfunction "AVDD_3_15") (pintype "passive"))
      (node (ref "U5") (pin "30") (pinfunction "AVDD_4_30") (pintype "passive"))
      (node (ref "U5") (pin "6") (pinfunction "AVDD_2_6") (pintype "passive"))
      (node (ref "U5") (pin "71") (pinfunction "AVDD_71") (pintype "passive"))
    )
    (net (code "2") (name "+5V_CURR_LIM") (class "Default")
      (node (ref "LED2") (pin "A") (pinfunction "A_A") (pintype "passive"))
      (node (ref "R5") (pin "1") (pinfunction "1_1") (pintype "passive"))
    )
    (net (code "3") (name "3_3V") (class "Default")
      (node (ref "SV1") (pin "17") (pinfunction "17_17") (pintype "passive"))
    )
    (net (code "4") (name "ADC2_0") (class "Default")
      (node (ref "J32") (pin "3") (pinfunction "3_3") (pintype "input"))
      (node (ref "JP4") (pin "1") (pinfunction "1_1") (pintype "passive"))
      (node (ref "U5") (pin "28") (pinfunction "V0A_28") (pintype "passive"))
    )
    (net (code "5") (name "ADC2_1") (class "Default")
      (node (ref "J31") (pin "3") (pinfunction "3_3") (pintype "input"))
      (node (ref "JP4") (pin "3") (pinfunction "3_3") (pintype "passive"))
      (node (ref "U5") (pin "26") (pinfunction "V1A_26") (pintype "passive"))
    )
    (net (code "6") (name "ADC2_2") (class "Default")
      (node (ref "J30") (pin "3") (pinfunction "3_3") (pintype "input"))
      (node (ref "JP4") (pin "5") (pinfunction "5_5") (pintype "passive"))
      (node (ref "U5") (pin "24") (pinfunction "V2A_24") (pintype "passive"))
    )
    (net (code "7") (name "ADC2_3") (class "Default")
      (node (ref "J29") (pin "3") (pinfunction "3_3") (pintype "input"))
      (node (ref "JP4") (pin "7") (pinfunction "7_7") (pintype "passive"))
      (node (ref "U5") (pin "22") (pinfunction "V3A_22") (pintype "passive"))
    )
    (net (code "8") (name "ADC2_4") (class "Default")
      (node (ref "J28") (pin "3") (pinfunction "3_3") (pintype "input"))
      (node (ref "JP4") (pin "9") (pinfunction "9_9") (pintype "passive"))
      (node (ref "U5") (pin "19") (pinfunction "V4A_19") (pintype "passive"))
    )
    (net (code "9") (name "ADC2_5") (class "Default")
      (node (ref "J27") (pin "3") (pinfunction "3_3") (pintype "input"))
      (node (ref "JP4") (pin "11") (pinfunction "11_11") (pintype "passive"))
      (node (ref "U5") (pin "17") (pinfunction "V5A_17") (pintype "passive"))
    )
    (net (code "10") (name "ADC2_6") (class "Default")
      (node (ref "J26") (pin "3") (pinfunction "3_3") (pintype "input"))
      (node (ref "JP4") (pin "13") (pinfunction "13_13") (pintype "passive"))
      (node (ref "U5") (pin "14") (pinfunction "V6A_14") (pintype "passive"))
    )
    (net (code "11") (name "ADC2_7") (class "Default")
      (node (ref "J25") (pin "3") (pinfunction "3_3") (pintype "input"))
      (node (ref "JP4") (pin "15") (pinfunction "15_15") (pintype "passive"))
      (node (ref "U5") (pin "12") (pinfunction "V7A_12") (pintype "passive"))
    )
    (net (code "12") (name "ADC2_8") (class "Default")
      (node (ref "J17") (pin "3") (pinfunction "3_3") (pintype "input"))
      (node (ref "JP3") (pin "15") (pinfunction "15_15") (pintype "passive"))
      (node (ref "U5") (pin "73") (pinfunction "V0B_73") (pintype "passive"))
    )
    (net (code "13") (name "ADC2_9") (class "Default")
      (node (ref "J18") (pin "3") (pinfunction "3_3") (pintype "input"))
      (node (ref "JP3") (pin "13") (pinfunction "13_13") (pintype "passive"))
      (node (ref "U5") (pin "75") (pinfunction "V1B_75") (pintype "passive"))
    )
    (net (code "14") (name "ADC2_10") (class "Default")
      (node (ref "J19") (pin "3") (pinfunction "3_3") (pintype "input"))
      (node (ref "JP3") (pin "11") (pinfunction "11_11") (pintype "passive"))
      (node (ref "U5") (pin "77") (pinfunction "V2B_77") (pintype "passive"))
    )
    (net (code "15") (name "ADC2_11") (class "Default")
      (node (ref "J20") (pin "3") (pinfunction "3_3") (pintype "input"))
      (node (ref "JP3") (pin "9") (pinfunction "9_9") (pintype "passive"))
      (node (ref "U5") (pin "79") (pinfunction "V3B_79") (pintype "passive"))
    )
    (net (code "16") (name "ADC2_12") (class "Default")
      (node (ref "J21") (pin "3") (pinfunction "3_3") (pintype "input"))
      (node (ref "JP3") (pin "7") (pinfunction "7_7") (pintype "passive"))
      (node (ref "U5") (pin "2") (pinfunction "V4B_2") (pintype "passive"))
    )
    (net (code "17") (name "ADC2_13") (class "Default")
      (node (ref "J22") (pin "3") (pinfunction "3_3") (pintype "input"))
      (node (ref "JP3") (pin "5") (pinfunction "5_5") (pintype "passive"))
      (node (ref "U5") (pin "4") (pinfunction "V5B_4") (pintype "passive"))
    )
    (net (code "18") (name "ADC2_14") (class "Default")
      (node (ref "J23") (pin "3") (pinfunction "3_3") (pintype "input"))
      (node (ref "JP3") (pin "3") (pinfunction "3_3") (pintype "passive"))
      (node (ref "U5") (pin "7") (pinfunction "V6B_7") (pintype "passive"))
    )
    (net (code "19") (name "ADC2_15") (class "Default")
      (node (ref "J24") (pin "3") (pinfunction "3_3") (pintype "input"))
      (node (ref "JP3") (pin "1") (pinfunction "1_1") (pintype "passive"))
      (node (ref "U5") (pin "9") (pinfunction "V7B_9") (pintype "passive"))
    )
    (net (code "20") (name "ADC_2_COM_MODE") (class "Default")
      (node (ref "R2") (pin "1") (pinfunction "1_1") (pintype "passive"))
      (node (ref "U5") (pin "40") (pinfunction "*PAR/SER_40") (pintype "passive"))
    )
    (net (code "21") (name "ADC_2_CONVST") (class "Default")
      (node (ref "SV1") (pin "5") (pinfunction "5_5") (pintype "passive"))
      (node (ref "U$1") (pin "2-OUT2") (pinfunction "2-OUT2_2-OUT2") (pintype "bidirectional"))
      (node (ref "U5") (pin "68") (pinfunction "CONVST_68") (pintype "passive"))
    )
    (net (code "22") (name "ADC_2_REFCAP") (class "Default")
      (node (ref "C45") (pin "2") (pinfunction "2_2") (pintype "passive"))
      (node (ref "U5") (pin "31") (pinfunction "REFCAP_31") (pintype "passive"))
    )
    (net (code "23") (name "ADC_2_REFINOUT") (class "Default")
      (node (ref "C62") (pin "2") (pinfunction "2_2") (pintype "passive"))
      (node (ref "R6") (pin "1") (pinfunction "1_1") (pintype "passive"))
      (node (ref "U5") (pin "33") (pinfunction "REFINOUT_33") (pintype "passive"))
    )
    (net (code "24") (name "ADC_2_REGCAP") (class "Default")
      (node (ref "C48") (pin "1") (pinfunction "1_1") (pintype "passive"))
      (node (ref "C49") (pin "1") (pinfunction "1_1") (pintype "passive"))
      (node (ref "U5") (pin "70") (pinfunction "REGCAP_70") (pintype "passive"))
    )
    (net (code "25") (name "ADC_2_REGCAPD") (class "Default")
      (node (ref "C50") (pin "1") (pinfunction "1_1") (pintype "passive"))
      (node (ref "C51") (pin "1") (pinfunction "1_1") (pintype "passive"))
      (node (ref "U5") (pin "52") (pinfunction "REGCAPD_52") (pintype "passive"))
    )
    (net (code "26") (name "ADC_2_RST") (class "Default")
      (node (ref "R4") (pin "1") (pinfunction "1_1") (pintype "passive"))
      (node (ref "S2") (pin "1") (pinfunction "S_1") (pintype "passive"))
      (node (ref "U5") (pin "36") (pinfunction "*RESET_36") (pintype "passive"))
    )
    (net (code "27") (name "ADC_2_VREF") (class "Default")
      (node (ref "C28") (pin "+") (pinfunction "+_+") (pintype "passive"))
      (node (ref "C35") (pin "1") (pinfunction "1_1") (pintype "passive"))
      (node (ref "C36") (pin "1") (pinfunction "1_1") (pintype "passive"))
      (node (ref "R6") (pin "2") (pinfunction "2_2") (pintype "passive"))
      (node (ref "U4") (pin "6") (pinfunction "VOUT_6") (pintype "passive"))
    )
    (net (code "28") (name "BT_1_AIN1_+") (class "Default")
      (node (ref "J49") (pin "3") (pinfunction "3_3") (pintype "passive"))
      (node (ref "JP10") (pin "2") (pinfunction "2_2") (pintype "passive"))
      (node (ref "U18") (pin "10") (pinfunction "AIN1(+)_10") (pintype "passive"))
    )
    (net (code "29") (name "BT_1_AIN1_-") (class "Default")
      (node (ref "J49") (pin "4") (pinfunction "4_4") (pintype "passive"))
      (node (ref "JP10") (pin "1") (pinfunction "1_1") (pintype "passive"))
      (node (ref "U18") (pin "11") (pinfunction "AIN1(-)_11") (pintype "passive"))
    )
    (net (code "30") (name "BT_1_AIN2_+") (class "Default")
      (node (ref "J50") (pin "3") (pinfunction "3_3") (pintype "passive"))
      (node (ref "JP10") (pin "4") (pinfunction "4_4") (pintype "passive"))
      (node (ref "U18") (pin "12") (pinfunction "AIN2(+)D1_12") (pintype "passive"))
    )
    (net (code "31") (name "BT_1_AIN2_-") (class "Default")
      (node (ref "J50") (pin "4") (pinfunction "4_4") (pintype "passive"))
      (node (ref "JP10") (pin "3") (pinfunction "3_3") (pintype "passive"))
      (node (ref "U18") (pin "13") (pinfunction "AIN2(-)D0_13") (pintype "passive"))
    )
    (net (code "32") (name "BT_1_MCLK_OUT") (class "Default")
      (node (ref "U18") (pin "3") (pinfunction "MCLK_OUT_3") (pintype "passive"))
      (node (ref "U21") (pin "2") (pinfunction "MCLK_IN_2") (pintype "passive"))
    )
    (net (code "33") (name "BT_2_AIN1_+") (class "Default")
      (node (ref "J51") (pin "3") (pinfunction "3_3") (pintype "passive"))
      (node (ref "JP10") (pin "6") (pinfunction "6_6") (pintype "passive"))
      (node (ref "U21") (pin "10") (pinfunction "AIN1(+)_10") (pintype "passive"))
    )
    (net (code "34") (name "BT_2_AIN1_-") (class "Default")
      (node (ref "J51") (pin "4") (pinfunction "4_4") (pintype "passive"))
      (node (ref "JP10") (pin "5") (pinfunction "5_5") (pintype "passive"))
      (node (ref "U21") (pin "11") (pinfunction "AIN1(-)_11") (pintype "passive"))
    )
    (net (code "35") (name "BT_2_AIN2_+") (class "Default")
      (node (ref "J52") (pin "3") (pinfunction "3_3") (pintype "passive"))
      (node (ref "JP10") (pin "8") (pinfunction "8_8") (pintype "passive"))
      (node (ref "U21") (pin "12") (pinfunction "AIN2(+)D1_12") (pintype "passive"))
    )
    (net (code "36") (name "BT_2_AIN2_-") (class "Default")
      (node (ref "J52") (pin "4") (pinfunction "4_4") (pintype "passive"))
      (node (ref "JP10") (pin "7") (pinfunction "7_7") (pintype "passive"))
      (node (ref "U21") (pin "13") (pinfunction "AIN2(-)D0_13") (pintype "passive"))
    )
    (net (code "37") (name "BT_2_MCLK_OUT") (class "Default")
      (node (ref "U21") (pin "3") (pinfunction "MCLK_OUT_3") (pintype "passive"))
      (node (ref "U23") (pin "2") (pinfunction "MCLK_IN_2") (pintype "passive"))
    )
    (net (code "38") (name "BT_3_AIN1_+") (class "Default")
      (node (ref "J53") (pin "3") (pinfunction "3_3") (pintype "passive"))
      (node (ref "JP10") (pin "10") (pinfunction "10_10") (pintype "passive"))
      (node (ref "U23") (pin "10") (pinfunction "AIN1(+)_10") (pintype "passive"))
    )
    (net (code "39") (name "BT_3_AIN1_-") (class "Default")
      (node (ref "J53") (pin "4") (pinfunction "4_4") (pintype "passive"))
      (node (ref "JP10") (pin "9") (pinfunction "9_9") (pintype "passive"))
      (node (ref "U23") (pin "11") (pinfunction "AIN1(-)_11") (pintype "passive"))
    )
    (net (code "40") (name "BT_3_AIN2_+") (class "Default")
      (node (ref "J54") (pin "3") (pinfunction "3_3") (pintype "passive"))
      (node (ref "JP10") (pin "12") (pinfunction "12_12") (pintype "passive"))
      (node (ref "U23") (pin "12") (pinfunction "AIN2(+)D1_12") (pintype "passive"))
    )
    (net (code "41") (name "BT_3_AIN2_-") (class "Default")
      (node (ref "J54") (pin "4") (pinfunction "4_4") (pintype "passive"))
      (node (ref "JP10") (pin "11") (pinfunction "11_11") (pintype "passive"))
      (node (ref "U23") (pin "13") (pinfunction "AIN2(-)D0_13") (pintype "passive"))
    )
    (net (code "42") (name "BT_3_MCLK_OUT") (class "Default")
      (node (ref "U23") (pin "3") (pinfunction "MCLK_OUT_3") (pintype "passive"))
      (node (ref "U24") (pin "2") (pinfunction "MCLK_IN_2") (pintype "passive"))
    )
    (net (code "43") (name "BT_4_AIN1_+") (class "Default")
      (node (ref "J55") (pin "3") (pinfunction "3_3") (pintype "passive"))
      (node (ref "JP10") (pin "14") (pinfunction "14_14") (pintype "passive"))
      (node (ref "U24") (pin "10") (pinfunction "AIN1(+)_10") (pintype "passive"))
    )
    (net (code "44") (name "BT_4_AIN1_-") (class "Default")
      (node (ref "J55") (pin "4") (pinfunction "4_4") (pintype "passive"))
      (node (ref "JP10") (pin "13") (pinfunction "13_13") (pintype "passive"))
      (node (ref "U24") (pin "11") (pinfunction "AIN1(-)_11") (pintype "passive"))
    )
    (net (code "45") (name "BT_4_AIN2_+") (class "Default")
      (node (ref "J56") (pin "3") (pinfunction "3_3") (pintype "passive"))
      (node (ref "JP10") (pin "16") (pinfunction "16_16") (pintype "passive"))
      (node (ref "U24") (pin "12") (pinfunction "AIN2(+)D1_12") (pintype "passive"))
    )
    (net (code "46") (name "BT_4_AIN2_-") (class "Default")
      (node (ref "J56") (pin "4") (pinfunction "4_4") (pintype "passive"))
      (node (ref "JP10") (pin "15") (pinfunction "15_15") (pintype "passive"))
      (node (ref "U24") (pin "13") (pinfunction "AIN2(-)D0_13") (pintype "passive"))
    )
    (net (code "47") (name "BT_4_MCLK_OUT") (class "Default")
      (node (ref "U25") (pin "2") (pinfunction "MCLK_IN_2") (pintype "passive"))
      (node (ref "Y1") (pin "3") (pinfunction "OUT_3") (pintype "bidirectional"))
    )
    (net (code "48") (name "BT_5_AIN1_+") (class "Default")
      (node (ref "J57") (pin "3") (pinfunction "3_3") (pintype "passive"))
      (node (ref "JP5") (pin "2") (pinfunction "2_2") (pintype "passive"))
      (node (ref "U25") (pin "10") (pinfunction "AIN1(+)_10") (pintype "passive"))
    )
    (net (code "49") (name "BT_5_AIN1_-") (class "Default")
      (node (ref "J57") (pin "4") (pinfunction "4_4") (pintype "passive"))
      (node (ref "JP5") (pin "1") (pinfunction "1_1") (pintype "passive"))
      (node (ref "U25") (pin "11") (pinfunction "AIN1(-)_11") (pintype "passive"))
    )
    (net (code "50") (name "BT_5_AIN2_+") (class "Default")
      (node (ref "J58") (pin "3") (pinfunction "3_3") (pintype "passive"))
      (node (ref "JP5") (pin "4") (pinfunction "4_4") (pintype "passive"))
      (node (ref "U25") (pin "12") (pinfunction "AIN2(+)D1_12") (pintype "passive"))
    )
    (net (code "51") (name "BT_5_AIN2_-") (class "Default")
      (node (ref "J58") (pin "4") (pinfunction "4_4") (pintype "passive"))
      (node (ref "JP5") (pin "3") (pinfunction "3_3") (pintype "passive"))
      (node (ref "U25") (pin "13") (pinfunction "AIN2(-)D0_13") (pintype "passive"))
    )
    (net (code "52") (name "BT_5_MCLK_OUT") (class "Default")
      (node (ref "U25") (pin "3") (pinfunction "MCLK_OUT_3") (pintype "passive"))
      (node (ref "U26") (pin "2") (pinfunction "MCLK_IN_2") (pintype "passive"))
    )
    (net (code "53") (name "BT_6_AIN1_+") (class "Default")
      (node (ref "J59") (pin "3") (pinfunction "3_3") (pintype "passive"))
      (node (ref "JP5") (pin "6") (pinfunction "6_6") (pintype "passive"))
      (node (ref "U26") (pin "10") (pinfunction "AIN1(+)_10") (pintype "passive"))
    )
    (net (code "54") (name "BT_6_AIN1_-") (class "Default")
      (node (ref "J59") (pin "4") (pinfunction "4_4") (pintype "passive"))
      (node (ref "JP5") (pin "5") (pinfunction "5_5") (pintype "passive"))
      (node (ref "U26") (pin "11") (pinfunction "AIN1(-)_11") (pintype "passive"))
    )
    (net (code "55") (name "BT_6_AIN2_+") (class "Default")
      (node (ref "J60") (pin "3") (pinfunction "3_3") (pintype "passive"))
      (node (ref "JP5") (pin "8") (pinfunction "8_8") (pintype "passive"))
      (node (ref "U26") (pin "12") (pinfunction "AIN2(+)D1_12") (pintype "passive"))
    )
    (net (code "56") (name "BT_6_AIN2_-") (class "Default")
      (node (ref "J60") (pin "4") (pinfunction "4_4") (pintype "passive"))
      (node (ref "JP5") (pin "7") (pinfunction "7_7") (pintype "passive"))
      (node (ref "U26") (pin "13") (pinfunction "AIN2(-)D0_13") (pintype "passive"))
    )
    (net (code "57") (name "BT_6_MCLK_OUT") (class "Default")
      (node (ref "U26") (pin "3") (pinfunction "MCLK_OUT_3") (pintype "passive"))
      (node (ref "U27") (pin "2") (pinfunction "MCLK_IN_2") (pintype "passive"))
    )
    (net (code "58") (name "BT_7_AIN1_+") (class "Default")
      (node (ref "J61") (pin "3") (pinfunction "3_3") (pintype "passive"))
      (node (ref "JP5") (pin "10") (pinfunction "10_10") (pintype "passive"))
      (node (ref "U27") (pin "10") (pinfunction "AIN1(+)_10") (pintype "passive"))
    )
    (net (code "59") (name "BT_7_AIN1_-") (class "Default")
      (node (ref "J61") (pin "4") (pinfunction "4_4") (pintype "passive"))
      (node (ref "JP5") (pin "9") (pinfunction "9_9") (pintype "passive"))
      (node (ref "U27") (pin "11") (pinfunction "AIN1(-)_11") (pintype "passive"))
    )
    (net (code "60") (name "BT_7_AIN2_+") (class "Default")
      (node (ref "J62") (pin "3") (pinfunction "3_3") (pintype "passive"))
      (node (ref "JP5") (pin "12") (pinfunction "12_12") (pintype "passive"))
      (node (ref "U27") (pin "12") (pinfunction "AIN2(+)D1_12") (pintype "passive"))
    )
    (net (code "61") (name "BT_7_AIN2_-") (class "Default")
      (node (ref "J62") (pin "4") (pinfunction "4_4") (pintype "passive"))
      (node (ref "JP5") (pin "11") (pinfunction "11_11") (pintype "passive"))
      (node (ref "U27") (pin "13") (pinfunction "AIN2(-)D0_13") (pintype "passive"))
    )
    (net (code "62") (name "BT_7_MCLK_OUT") (class "Default")
      (node (ref "U27") (pin "3") (pinfunction "MCLK_OUT_3") (pintype "passive"))
      (node (ref "U28") (pin "2") (pinfunction "MCLK_IN_2") (pintype "passive"))
    )
    (net (code "63") (name "BT_8_AIN1_+") (class "Default")
      (node (ref "J63") (pin "3") (pinfunction "3_3") (pintype "passive"))
      (node (ref "JP5") (pin "14") (pinfunction "14_14") (pintype "passive"))
      (node (ref "U28") (pin "10") (pinfunction "AIN1(+)_10") (pintype "passive"))
    )
    (net (code "64") (name "BT_8_AIN1_-") (class "Default")
      (node (ref "J63") (pin "4") (pinfunction "4_4") (pintype "passive"))
      (node (ref "JP5") (pin "13") (pinfunction "13_13") (pintype "passive"))
      (node (ref "U28") (pin "11") (pinfunction "AIN1(-)_11") (pintype "passive"))
    )
    (net (code "65") (name "BT_8_AIN2_+") (class "Default")
      (node (ref "J64") (pin "3") (pinfunction "3_3") (pintype "passive"))
      (node (ref "JP5") (pin "16") (pinfunction "16_16") (pintype "passive"))
      (node (ref "U28") (pin "12") (pinfunction "AIN2(+)D1_12") (pintype "passive"))
    )
    (net (code "66") (name "BT_8_AIN2_-") (class "Default")
      (node (ref "J64") (pin "4") (pinfunction "4_4") (pintype "passive"))
      (node (ref "JP5") (pin "15") (pinfunction "15_15") (pintype "passive"))
      (node (ref "U28") (pin "13") (pinfunction "AIN2(-)D0_13") (pintype "passive"))
    )
    (net (code "67") (name "DAC2_0") (class "Default")
      (node (ref "JP2") (pin "15") (pinfunction "15_15") (pintype "passive"))
      (node (ref "U19") (pin "34") (pinfunction "VOUT0_34") (pintype "passive"))
      (node (ref "U2") (pin "15") (pinfunction "15_15") (pintype "passive"))
    )
    (net (code "68") (name "DAC2_1") (class "Default")
      (node (ref "JP2") (pin "13") (pinfunction "13_13") (pintype "passive"))
      (node (ref "U19") (pin "35") (pinfunction "VOUT1_35") (pintype "passive"))
      (node (ref "U2") (pin "13") (pinfunction "13_13") (pintype "passive"))
    )
    (net (code "69") (name "DAC2_2") (class "Default")
      (node (ref "JP2") (pin "11") (pinfunction "11_11") (pintype "passive"))
      (node (ref "U19") (pin "36") (pinfunction "VOUT2_36") (pintype "passive"))
      (node (ref "U2") (pin "11") (pinfunction "11_11") (pintype "passive"))
    )
    (net (code "70") (name "DAC2_3") (class "Default")
      (node (ref "JP2") (pin "9") (pinfunction "9_9") (pintype "passive"))
      (node (ref "U19") (pin "37") (pinfunction "VOUT3_37") (pintype "passive"))
      (node (ref "U2") (pin "9") (pinfunction "9_9") (pintype "passive"))
    )
    (net (code "71") (name "DAC2_4") (class "Default")
      (node (ref "JP2") (pin "7") (pinfunction "7_7") (pintype "passive"))
      (node (ref "U19") (pin "39") (pinfunction "VOUT4_39") (pintype "passive"))
      (node (ref "U2") (pin "7") (pinfunction "7_7") (pintype "passive"))
    )
    (net (code "72") (name "DAC2_5") (class "Default")
      (node (ref "JP2") (pin "5") (pinfunction "5_5") (pintype "passive"))
      (node (ref "U19") (pin "40") (pinfunction "VOUT5_40") (pintype "passive"))
      (node (ref "U2") (pin "5") (pinfunction "5_5") (pintype "passive"))
    )
    (net (code "73") (name "DAC2_6") (class "Default")
      (node (ref "JP2") (pin "3") (pinfunction "3_3") (pintype "passive"))
      (node (ref "U19") (pin "41") (pinfunction "VOUT6_41") (pintype "passive"))
      (node (ref "U2") (pin "3") (pinfunction "3_3") (pintype "passive"))
    )
    (net (code "74") (name "DAC2_7") (class "Default")
      (node (ref "JP2") (pin "1") (pinfunction "1_1") (pintype "passive"))
      (node (ref "U19") (pin "42") (pinfunction "VOUT7_42") (pintype "passive"))
      (node (ref "U2") (pin "1") (pinfunction "1_1") (pintype "passive"))
    )
    (net (code "75") (name "DAC2_8") (class "Default")
      (node (ref "JP2") (pin "31") (pinfunction "31_31") (pintype "passive"))
      (node (ref "U19") (pin "15") (pinfunction "VOUT8_15") (pintype "passive"))
      (node (ref "U2") (pin "31") (pinfunction "31_31") (pintype "passive"))
    )
    (net (code "76") (name "DAC2_9") (class "Default")
      (node (ref "JP2") (pin "29") (pinfunction "29_29") (pintype "passive"))
      (node (ref "U19") (pin "16") (pinfunction "VOUT9_16") (pintype "passive"))
      (node (ref "U2") (pin "29") (pinfunction "29_29") (pintype "passive"))
    )
    (net (code "77") (name "DAC2_10") (class "Default")
      (node (ref "JP2") (pin "27") (pinfunction "27_27") (pintype "passive"))
      (node (ref "U19") (pin "17") (pinfunction "VOUT10_17") (pintype "passive"))
      (node (ref "U2") (pin "27") (pinfunction "27_27") (pintype "passive"))
    )
    (net (code "78") (name "DAC2_11") (class "Default")
      (node (ref "JP2") (pin "25") (pinfunction "25_25") (pintype "passive"))
      (node (ref "U19") (pin "18") (pinfunction "VOUT11_18") (pintype "passive"))
      (node (ref "U2") (pin "25") (pinfunction "25_25") (pintype "passive"))
    )
    (net (code "79") (name "DAC2_12") (class "Default")
      (node (ref "JP2") (pin "23") (pinfunction "23_23") (pintype "passive"))
      (node (ref "U19") (pin "20") (pinfunction "VOUT12_20") (pintype "passive"))
      (node (ref "U2") (pin "23") (pinfunction "23_23") (pintype "passive"))
    )
    (net (code "80") (name "DAC2_13") (class "Default")
      (node (ref "JP2") (pin "21") (pinfunction "21_21") (pintype "passive"))
      (node (ref "U19") (pin "21") (pinfunction "VOUT13_21") (pintype "passive"))
      (node (ref "U2") (pin "21") (pinfunction "21_21") (pintype "passive"))
    )
    (net (code "81") (name "DAC2_14") (class "Default")
      (node (ref "JP2") (pin "19") (pinfunction "19_19") (pintype "passive"))
      (node (ref "U19") (pin "22") (pinfunction "VOUT14_22") (pintype "passive"))
      (node (ref "U2") (pin "19") (pinfunction "19_19") (pintype "passive"))
    )
    (net (code "82") (name "DAC2_15") (class "Default")
      (node (ref "JP2") (pin "17") (pinfunction "17_17") (pintype "passive"))
      (node (ref "U19") (pin "23") (pinfunction "VOUT15_23") (pintype "passive"))
      (node (ref "U2") (pin "17") (pinfunction "17_17") (pintype "passive"))
    )
    (net (code "83") (name "DAC_2_CLR") (class "Default")
      (node (ref "R20") (pin "2") (pinfunction "2_2") (pintype "passive"))
      (node (ref "U19") (pin "2") (pinfunction "*CLR_2") (pintype "passive"))
    )
    (net (code "84") (name "DAC_2_RST") (class "Default")
      (node (ref "R19") (pin "2") (pinfunction "2_2") (pintype "passive"))
      (node (ref "S8") (pin "4") (pinfunction "P1_4") (pintype "passive"))
      (node (ref "U19") (pin "3") (pinfunction "*RESET_3") (pintype "passive"))
    )
    (net (code "85") (name "DVCC") (class "Default")
      (node (ref "C1") (pin "2") (pinfunction "2_2") (pintype "passive"))
      (node (ref "C11") (pin "2") (pinfunction "2_2") (pintype "passive"))
      (node (ref "C136") (pin "1") (pinfunction "1_1") (pintype "passive"))
      (node (ref "C137") (pin "1") (pinfunction "1_1") (pintype "passive"))
      (node (ref "C14") (pin "+") (pinfunction "+_+") (pintype "passive"))
      (node (ref "C19") (pin "1") (pinfunction "1_1") (pintype "passive"))
      (node (ref "C2") (pin "1") (pinfunction "1_1") (pintype "passive"))
      (node (ref "C20") (pin "1") (pinfunction "1_1") (pintype "passive"))
      (node (ref "C21") (pin "+") (pinfunction "+_+") (pintype "passive"))
      (node (ref "C22") (pin "+") (pinfunction "+_+") (pintype "passive"))
      (node (ref "C3") (pin "1") (pinfunction "1_1") (pintype "passive"))
      (node (ref "C4") (pin "1") (pinfunction "1_1") (pintype "passive"))
      (node (ref "C46") (pin "1") (pinfunction "1_1") (pintype "passive"))
      (node (ref "C47") (pin "1") (pinfunction "1_1") (pintype "passive"))
      (node (ref "C5") (pin "1") (pinfunction "1_1") (pintype "passive"))
      (node (ref "C6") (pin "1") (pinfunction "1_1") (pintype "passive"))
      (node (ref "C7") (pin "1") (pinfunction "1_1") (pintype "passive"))
      (node (ref "PL1") (pin "2") (pinfunction "S_2") (pintype "passive"))
      (node (ref "Q1") (pin "C") (pinfunction "C_C") (pintype "passive"))
      (node (ref "R19") (pin "1") (pinfunction "1_1") (pintype "passive"))
      (node (ref "R2") (pin "2") (pinfunction "2_2") (pintype "passive"))
      (node (ref "R20") (pin "1") (pinfunction "1_1") (pintype "passive"))
      (node (ref "R3") (pin "2") (pinfunction "2_2") (pintype "passive"))
      (node (ref "R4") (pin "2") (pinfunction "2_2") (pintype "passive"))
      (node (ref "U18") (pin "18") (pinfunction "*STANDBY_18") (pintype "passive"))
      (node (ref "U18") (pin "23") (pinfunction "DVDD_23") (pintype "passive"))
      (node (ref "U18") (pin "5") (pinfunction "*SYNC_5") (pintype "passive"))
      (node (ref "U18") (pin "6") (pinfunction "*RESET_6") (pintype "passive"))
      (node (ref "U19") (pin "44") (pinfunction "DVCC_2_44") (pintype "passive"))
      (node (ref "U19") (pin "50") (pinfunction "DVCC_50") (pintype "passive"))
      (node (ref "U21") (pin "18") (pinfunction "*STANDBY_18") (pintype "passive"))
      (node (ref "U21") (pin "23") (pinfunction "DVDD_23") (pintype "passive"))
      (node (ref "U21") (pin "5") (pinfunction "*SYNC_5") (pintype "passive"))
      (node (ref "U21") (pin "6") (pinfunction "*RESET_6") (pintype "passive"))
      (node (ref "U23") (pin "18") (pinfunction "*STANDBY_18") (pintype "passive"))
      (node (ref "U23") (pin "23") (pinfunction "DVDD_23") (pintype "passive"))
      (node (ref "U23") (pin "5") (pinfunction "*SYNC_5") (pintype "passive"))
      (node (ref "U23") (pin "6") (pinfunction "*RESET_6") (pintype "passive"))
      (node (ref "U24") (pin "18") (pinfunction "*STANDBY_18") (pintype "passive"))
      (node (ref "U24") (pin "23") (pinfunction "DVDD_23") (pintype "passive"))
      (node (ref "U24") (pin "5") (pinfunction "*SYNC_5") (pintype "passive"))
      (node (ref "U24") (pin "6") (pinfunction "*RESET_6") (pintype "passive"))
      (node (ref "U25") (pin "18") (pinfunction "*STANDBY_18") (pintype "passive"))
      (node (ref "U25") (pin "23") (pinfunction "DVDD_23") (pintype "passive"))
      (node (ref "U25") (pin "5") (pinfunction "*SYNC_5") (pintype "passive"))
      (node (ref "U25") (pin "6") (pinfunction "*RESET_6") (pintype "passive"))
      (node (ref "U26") (pin "18") (pinfunction "*STANDBY_18") (pintype "passive"))
      (node (ref "U26") (pin "23") (pinfunction "DVDD_23") (pintype "passive"))
      (node (ref "U26") (pin "5") (pinfunction "*SYNC_5") (pintype "passive"))
      (node (ref "U26") (pin "6") (pinfunction "*RESET_6") (pintype "passive"))
      (node (ref "U27") (pin "18") (pinfunction "*STANDBY_18") (pintype "passive"))
      (node (ref "U27") (pin "23") (pinfunction "DVDD_23") (pintype "passive"))
      (node (ref "U27") (pin "5") (pinfunction "*SYNC_5") (pintype "passive"))
      (node (ref "U27") (pin "6") (pinfunction "*RESET_6") (pintype "passive"))
      (node (ref "U28") (pin "18") (pinfunction "*STANDBY_18") (pintype "passive"))
      (node (ref "U28") (pin "23") (pinfunction "DVDD_23") (pintype "passive"))
      (node (ref "U28") (pin "5") (pinfunction "*SYNC_5") (pintype "passive"))
      (node (ref "U28") (pin "6") (pinfunction "*RESET_6") (pintype "passive"))
      (node (ref "U5") (pin "49") (pinfunction "VDRIVE_49") (pintype "passive"))
      (node (ref "Y1") (pin "4") (pinfunction "VCC_4") (pintype "bidirectional"))
      (node (ref "Y3") (pin "4") (pinfunction "VCC_4") (pintype "bidirectional"))
    )
    (net (code "86") (name "DVCC_CURR_LIM") (class "Default")
      (node (ref "LED3") (pin "A") (pinfunction "A_A") (pintype "passive"))
      (node (ref "R3") (pin "1") (pinfunction "1_1") (pintype "passive"))
    )
    (net (code "87") (name "D_IO_1") (class "Default")
      (node (ref "JP13") (pin "2") (pinfunction "2_2") (pintype "passive"))
      (node (ref "U$1") (pin "7-RX2/OUT1A") (pinfunction "7-RX2/OUT1A_7-RX2/OUT1A") (pintype "bidirectional"))
    )
    (net (code "88") (name "D_IO_2") (class "Default")
      (node (ref "JP13") (pin "4") (pinfunction "4_4") (pintype "passive"))
      (node (ref "U$1") (pin "8-TX2/IN2") (pinfunction "8-TX2/IN1_8-TX2/IN2") (pintype "bidirectional"))
    )
    (net (code "89") (name "D_IO_3") (class "Default")
      (node (ref "JP13") (pin "6") (pinfunction "6_6") (pintype "passive"))
      (node (ref "U$1") (pin "9-OUT1C") (pinfunction "9-OUT1C_9-OUT1C") (pintype "bidirectional"))
    )
    (net (code "90") (name "D_IO_4") (class "Default")
      (node (ref "JP13") (pin "8") (pinfunction "8_8") (pintype "passive"))
      (node (ref "U$1") (pin "10-CS\\MQSR") (pinfunction "10-CS/MQSR_10-CS\\MQSR") (pintype "bidirectional"))
    )
    (net (code "91") (name "D_IO_5") (class "Default")
      (node (ref "JP13") (pin "10") (pinfunction "10_10") (pintype "passive"))
      (node (ref "U$1") (pin "25-A11/RX6/SDA2") (pinfunction "25-A11/RX6/SDA2_25-A11/RX6/SDA2") (pintype "bidirectional"))
    )
    (net (code "92") (name "D_IO_6") (class "Default")
      (node (ref "JP13") (pin "12") (pinfunction "12_12") (pintype "passive"))
      (node (ref "U$1") (pin "26-A12/MOSI1") (pinfunction "26-A12/MOSI1_26-A12/MOSI1") (pintype "bidirectional"))
    )
    (net (code "93") (name "D_IO_7") (class "Default")
      (node (ref "JP13") (pin "14") (pinfunction "14_14") (pintype "passive"))
      (node (ref "U$1") (pin "27-A13/SCK1") (pinfunction "27-A13/SCK1_27-A13/SCK1") (pintype "bidirectional"))
    )
    (net (code "94") (name "D_IO_8") (class "Default")
      (node (ref "JP13") (pin "16") (pinfunction "16_16") (pintype "passive"))
      (node (ref "U$1") (pin "28-RX7") (pinfunction "28-RX7_28-RX7") (pintype "bidirectional"))
    )
    (net (code "95") (name "D_IO_9") (class "Default")
      (node (ref "JP13") (pin "18") (pinfunction "18_18") (pintype "passive"))
      (node (ref "U$1") (pin "29-TX7") (pinfunction "29-TX7_29-TX7") (pintype "bidirectional"))
    )
    (net (code "96") (name "D_IO_10") (class "Default")
      (node (ref "JP13") (pin "20") (pinfunction "20_20") (pintype "passive"))
      (node (ref "U$1") (pin "30-CRX3") (pinfunction "30-CRX3_30-CRX3") (pintype "bidirectional"))
    )
    (net (code "97") (name "D_IO_11") (class "Default")
      (node (ref "JP13") (pin "22") (pinfunction "22_22") (pintype "passive"))
      (node (ref "U$1") (pin "31-CTX3") (pinfunction "31-CTX3_31-CTX3") (pintype "bidirectional"))
    )
    (net (code "98") (name "D_IO_12") (class "Default")
      (node (ref "JP13") (pin "24") (pinfunction "24_24") (pintype "passive"))
      (node (ref "U$1") (pin "32-OUT1B") (pinfunction "32-OUT1B_32-OUT1B") (pintype "bidirectional"))
    )
    (net (code "99") (name "GND") (class "Default")
      (node (ref "C1") (pin "1") (pinfunction "1_1") (pintype "passive"))
      (node (ref "C10") (pin "-") (pinfunction "-_-") (pintype "passive"))
      (node (ref "C11") (pin "1") (pinfunction "1_1") (pintype "passive"))
      (node (ref "C12") (pin "-") (pinfunction "-_-") (pintype "passive"))
      (node (ref "C13") (pin "-") (pinfunction "-_-") (pintype "passive"))
      (node (ref "C136") (pin "2") (pinfunction "2_2") (pintype "passive"))
      (node (ref "C137") (pin "2") (pinfunction "2_2") (pintype "passive"))
      (node (ref "C14") (pin "-") (pinfunction "-_-") (pintype "passive"))
      (node (ref "C141") (pin "2") (pinfunction "2_2") (pintype "passive"))
      (node (ref "C143") (pin "2") (pinfunction "2_2") (pintype "passive"))
      (node (ref "C145") (pin "2") (pinfunction "2_2") (pintype "passive"))
      (node (ref "C147") (pin "2") (pinfunction "2_2") (pintype "passive"))
      (node (ref "C148") (pin "2") (pinfunction "2_2") (pintype "passive"))
      (node (ref "C15") (pin "-") (pinfunction "-_-") (pintype "passive"))
      (node (ref "C150") (pin "2") (pinfunction "2_2") (pintype "passive"))
      (node (ref "C151") (pin "2") (pinfunction "2_2") (pintype "passive"))
      (node (ref "C16") (pin "+") (pinfunction "+_+") (pintype "passive"))
      (node (ref "C19") (pin "2") (pinfunction "2_2") (pintype "passive"))
      (node (ref "C2") (pin "2") (pinfunction "2_2") (pintype "passive"))
      (node (ref "C20") (pin "2") (pinfunction "2_2") (pintype "passive"))
      (node (ref "C21") (pin "-") (pinfunction "-_-") (pintype "passive"))
      (node (ref "C22") (pin "-") (pinfunction "-_-") (pintype "passive"))
      (node (ref "C23") (pin "-") (pinfunction "-_-") (pintype "passive"))
      (node (ref "C24") (pin "-") (pinfunction "-_-") (pintype "passive"))
      (node (ref "C25") (pin "+") (pinfunction "+_+") (pintype "passive"))
      (node (ref "C26") (pin "+") (pinfunction "+_+") (pintype "passive"))
      (node (ref "C27") (pin "-") (pinfunction "-_-") (pintype "passive"))
      (node (ref "C28") (pin "-") (pinfunction "-_-") (pintype "passive"))
      (node (ref "C3") (pin "2") (pinfunction "2_2") (pintype "passive"))
      (node (ref "C32") (pin "2") (pinfunction "2_2") (pintype "passive"))
      (node (ref "C33") (pin "2") (pinfunction "2_2") (pintype "passive"))
      (node (ref "C35") (pin "2") (pinfunction "2_2") (pintype "passive"))
      (node (ref "C36") (pin "2") (pinfunction "2_2") (pintype "passive"))
      (node (ref "C38") (pin "2") (pinfunction "2_2") (pintype "passive"))
      (node (ref "C39") (pin "2") (pinfunction "2_2") (pintype "passive"))
      (node (ref "C4") (pin "2") (pinfunction "2_2") (pintype "passive"))
      (node (ref "C40") (pin "2") (pinfunction "2_2") (pintype "passive"))
      (node (ref "C41") (pin "2") (pinfunction "2_2") (pintype "passive"))
      (node (ref "C42") (pin "2") (pinfunction "2_2") (pintype "passive"))
      (node (ref "C43") (pin "2") (pinfunction "2_2") (pintype "passive"))
      (node (ref "C44") (pin "2") (pinfunction "2_2") (pintype "passive"))
      (node (ref "C45") (pin "1") (pinfunction "1_1") (pintype "passive"))
      (node (ref "C46") (pin "2") (pinfunction "2_2") (pintype "passive"))
      (node (ref "C47") (pin "2") (pinfunction "2_2") (pintype "passive"))
      (node (ref "C48") (pin "2") (pinfunction "2_2") (pintype "passive"))
      (node (ref "C49") (pin "2") (pinfunction "2_2") (pintype "passive"))
      (node (ref "C5") (pin "2") (pinfunction "2_2") (pintype "passive"))
      (node (ref "C50") (pin "2") (pinfunction "2_2") (pintype "passive"))
      (node (ref "C51") (pin "2") (pinfunction "2_2") (pintype "passive"))
      (node (ref "C6") (pin "2") (pinfunction "2_2") (pintype "passive"))
      (node (ref "C62") (pin "1") (pinfunction "1_1") (pintype "passive"))
      (node (ref "C7") (pin "2") (pinfunction "2_2") (pintype "passive"))
      (node (ref "C8") (pin "-") (pinfunction "-_-") (pintype "passive"))
      (node (ref "C9") (pin "-") (pinfunction "-_-") (pintype "passive"))
      (node (ref "J17") (pin "2") (pinfunction "2_2") (pintype "input"))
      (node (ref "J18") (pin "2") (pinfunction "2_2") (pintype "input"))
      (node (ref "J19") (pin "2") (pinfunction "2_2") (pintype "input"))
      (node (ref "J20") (pin "2") (pinfunction "2_2") (pintype "input"))
      (node (ref "J21") (pin "2") (pinfunction "2_2") (pintype "input"))
      (node (ref "J22") (pin "2") (pinfunction "2_2") (pintype "input"))
      (node (ref "J23") (pin "2") (pinfunction "2_2") (pintype "input"))
      (node (ref "J24") (pin "2") (pinfunction "2_2") (pintype "input"))
      (node (ref "J25") (pin "2") (pinfunction "2_2") (pintype "input"))
      (node (ref "J26") (pin "2") (pinfunction "2_2") (pintype "input"))
      (node (ref "J27") (pin "2") (pinfunction "2_2") (pintype "input"))
      (node (ref "J28") (pin "2") (pinfunction "2_2") (pintype "input"))
      (node (ref "J29") (pin "2") (pinfunction "2_2") (pintype "input"))
      (node (ref "J30") (pin "2") (pinfunction "2_2") (pintype "input"))
      (node (ref "J31") (pin "2") (pinfunction "2_2") (pintype "input"))
      (node (ref "J32") (pin "2") (pinfunction "2_2") (pintype "input"))
      (node (ref "J49") (pin "2") (pinfunction "2_2") (pintype "passive"))
      (node (ref "J50") (pin "2") (pinfunction "2_2") (pintype "passive"))
      (node (ref "J51") (pin "2") (pinfunction "2_2") (pintype "passive"))
      (node (ref "J52") (pin "2") (pinfunction "2_2") (pintype "passive"))
      (node (ref "J53") (pin "2") (pinfunction "2_2") (pintype "passive"))
      (node (ref "J54") (pin "2") (pinfunction "2_2") (pintype "passive"))
      (node (ref "J55") (pin "2") (pinfunction "2_2") (pintype "passive"))
      (node (ref "J56") (pin "2") (pinfunction "2_2") (pintype "passive"))
      (node (ref "J57") (pin "2") (pinfunction "2_2") (pintype "passive"))
      (node (ref "J58") (pin "2") (pinfunction "2_2") (pintype "passive"))
      (node (ref "J59") (pin "2") (pinfunction "2_2") (pintype "passive"))
      (node (ref "J60") (pin "2") (pinfunction "2_2") (pintype "passive"))
      (node (ref "J61") (pin "2") (pinfunction "2_2") (pintype "passive"))
      (node (ref "J62") (pin "2") (pinfunction "2_2") (pintype "passive"))
      (node (ref "J63") (pin "2") (pinfunction "2_2") (pintype "passive"))
      (node (ref "J64") (pin "2") (pinfunction "2_2") (pintype "passive"))
      (node (ref "JP11") (pin "1") (pinfunction "1_1") (pintype "passive"))
      (node (ref "JP11") (pin "3") (pinfunction "3_3") (pintype "passive"))
      (node (ref "JP12") (pin "1") (pinfunction "1_1") (pintype "passive"))
      (node (ref "JP12") (pin "3") (pinfunction "3_3") (pintype "passive"))
      (node (ref "JP13") (pin "1") (pinfunction "1_1") (pintype "passive"))
      (node (ref "JP13") (pin "11") (pinfunction "11_11") (pintype "passive"))
      (node (ref "JP13") (pin "13") (pinfunction "13_13") (pintype "passive"))
      (node (ref "JP13") (pin "15") (pinfunction "15_15") (pintype "passive"))
      (node (ref "JP13") (pin "17") (pinfunction "17_17") (pintype "passive"))
      (node (ref "JP13") (pin "19") (pinfunction "19_19") (pintype "passive"))
      (node (ref "JP13") (pin "21") (pinfunction "21_21") (pintype "passive"))
      (node (ref "JP13") (pin "23") (pinfunction "23_23") (pintype "passive"))
      (node (ref "JP13") (pin "3") (pinfunction "3_3") (pintype "passive"))
      (node (ref "JP13") (pin "5") (pinfunction "5_5") (pintype "passive"))
      (node (ref "JP13") (pin "7") (pinfunction "7_7") (pintype "passive"))
      (node (ref "JP13") (pin "9") (pinfunction "9_9") (pintype "passive"))
      (node (ref "JP2") (pin "10") (pinfunction "10_10") (pintype "passive"))
      (node (ref "JP2") (pin "12") (pinfunction "12_12") (pintype "passive"))
      (node (ref "JP2") (pin "14") (pinfunction "14_14") (pintype "passive"))
      (node (ref "JP2") (pin "16") (pinfunction "16_16") (pintype "passive"))
      (node (ref "JP2") (pin "18") (pinfunction "18_18") (pintype "passive"))
      (node (ref "JP2") (pin "2") (pinfunction "2_2") (pintype "passive"))
      (node (ref "JP2") (pin "20") (pinfunction "20_20") (pintype "passive"))
      (node (ref "JP2") (pin "22") (pinfunction "22_22") (pintype "passive"))
      (node (ref "JP2") (pin "24") (pinfunction "24_24") (pintype "passive"))
      (node (ref "JP2") (pin "26") (pinfunction "26_26") (pintype "passive"))
      (node (ref "JP2") (pin "28") (pinfunction "28_28") (pintype "passive"))
      (node (ref "JP2") (pin "30") (pinfunction "30_30") (pintype "passive"))
      (node (ref "JP2") (pin "32") (pinfunction "32_32") (pintype "passive"))
      (node (ref "JP2") (pin "4") (pinfunction "4_4") (pintype "passive"))
      (node (ref "JP2") (pin "6") (pinfunction "6_6") (pintype "passive"))
      (node (ref "JP2") (pin "8") (pinfunction "8_8") (pintype "passive"))
      (node (ref "JP3") (pin "10") (pinfunction "10_10") (pintype "passive"))
      (node (ref "JP3") (pin "12") (pinfunction "12_12") (pintype "passive"))
      (node (ref "JP3") (pin "14") (pinfunction "14_14") (pintype "passive"))
      (node (ref "JP3") (pin "16") (pinfunction "16_16") (pintype "passive"))
      (node (ref "JP3") (pin "2") (pinfunction "2_2") (pintype "passive"))
      (node (ref "JP3") (pin "4") (pinfunction "4_4") (pintype "passive"))
      (node (ref "JP3") (pin "6") (pinfunction "6_6") (pintype "passive"))
      (node (ref "JP3") (pin "8") (pinfunction "8_8") (pintype "passive"))
      (node (ref "JP4") (pin "10") (pinfunction "10_10") (pintype "passive"))
      (node (ref "JP4") (pin "12") (pinfunction "12_12") (pintype "passive"))
      (node (ref "JP4") (pin "14") (pinfunction "14_14") (pintype "passive"))
      (node (ref "JP4") (pin "16") (pinfunction "16_16") (pintype "passive"))
      (node (ref "JP4") (pin "2") (pinfunction "2_2") (pintype "passive"))
      (node (ref "JP4") (pin "4") (pinfunction "4_4") (pintype "passive"))
      (node (ref "JP4") (pin "6") (pinfunction "6_6") (pintype "passive"))
      (node (ref "JP4") (pin "8") (pinfunction "8_8") (pintype "passive"))
      (node (ref "JP8") (pin "3") (pinfunction "3_3") (pintype "passive"))
      (node (ref "LED1") (pin "C") (pinfunction "C_C") (pintype "passive"))
      (node (ref "LED2") (pin "C") (pinfunction "C_C") (pintype "passive"))
      (node (ref "LED3") (pin "C") (pinfunction "C_C") (pintype "passive"))
      (node (ref "LED4") (pin "C") (pinfunction "C_C") (pintype "passive"))
      (node (ref "LED5") (pin "C") (pinfunction "C_C") (pintype "passive"))
      (node (ref "PL1") (pin "15") (pinfunction "S_15") (pintype "passive"))
      (node (ref "PL1") (pin "17") (pinfunction "S_17") (pintype "passive"))
      (node (ref "PL1") (pin "18") (pinfunction "S_18") (pintype "passive"))
      (node (ref "PL1") (pin "19") (pinfunction "S_19") (pintype "passive"))
      (node (ref "PL1") (pin "24") (pinfunction "S_24") (pintype "passive"))
      (node (ref "PL1") (pin "3") (pinfunction "S_3") (pintype "passive"))
      (node (ref "PL1") (pin "5") (pinfunction "S_5") (pintype "passive"))
      (node (ref "PL1") (pin "7") (pinfunction "S_7") (pintype "passive"))
      (node (ref "S1") (pin "3") (pinfunction "3_3") (pintype "passive"))
      (node (ref "S2") (pin "3") (pinfunction "P_3") (pintype "passive"))
      (node (ref "S2") (pin "4") (pinfunction "P1_4") (pintype "passive"))
      (node (ref "S8") (pin "1") (pinfunction "S_1") (pintype "passive"))
      (node (ref "S8") (pin "2") (pinfunction "S1_2") (pintype "passive"))
      (node (ref "SV1") (pin "14") (pinfunction "14_14") (pintype "passive"))
      (node (ref "SV1") (pin "20") (pinfunction "20_20") (pintype "passive"))
      (node (ref "SV1") (pin "25") (pinfunction "25_25") (pintype "passive"))
      (node (ref "SV1") (pin "30") (pinfunction "30_30") (pintype "passive"))
      (node (ref "SV1") (pin "34") (pinfunction "34_34") (pintype "passive"))
      (node (ref "SV1") (pin "39") (pinfunction "39_39") (pintype "passive"))
      (node (ref "SV1") (pin "6") (pinfunction "6_6") (pintype "passive"))
      (node (ref "SV1") (pin "9") (pinfunction "9_9") (pintype "passive"))
      (node (ref "U$1") (pin "GND1") (pinfunction "GND1_GND1") (pintype "bidirectional"))
      (node (ref "U$1") (pin "GND3") (pinfunction "GND3_GND3") (pintype "bidirectional"))
      (node (ref "U$1") (pin "GND6") (pinfunction "GND6_GND6") (pintype "bidirectional"))
      (node (ref "U18") (pin "15") (pinfunction "REF_IN(-)_15") (pintype "passive"))
      (node (ref "U18") (pin "24") (pinfunction "DGND_24") (pintype "passive"))
      (node (ref "U18") (pin "4") (pinfunction "POL_4") (pintype "passive"))
      (node (ref "U18") (pin "8") (pinfunction "AGND_8") (pintype "passive"))
      (node (ref "U19") (pin "19") (pinfunction "SIGGND1_19") (pintype "passive"))
      (node (ref "U19") (pin "38") (pinfunction "SIGGND0_38") (pintype "passive"))
      (node (ref "U19") (pin "4") (pinfunction "*BIN/2SCOMP_4") (pintype "passive"))
      (node (ref "U19") (pin "43") (pinfunction "DGND_2_43") (pintype "passive"))
      (node (ref "U19") (pin "51") (pinfunction "DGND_51") (pintype "passive"))
      (node (ref "U19") (pin "52") (pinfunction "AGND_52") (pintype "passive"))
      (node (ref "U2") (pin "10") (pinfunction "10_10") (pintype "passive"))
      (node (ref "U2") (pin "12") (pinfunction "12_12") (pintype "passive"))
      (node (ref "U2") (pin "14") (pinfunction "14_14") (pintype "passive"))
      (node (ref "U2") (pin "16") (pinfunction "16_16") (pintype "passive"))
      (node (ref "U2") (pin "18") (pinfunction "18_18") (pintype "passive"))
      (node (ref "U2") (pin "2") (pinfunction "2_2") (pintype "passive"))
      (node (ref "U2") (pin "20") (pinfunction "20_20") (pintype "passive"))
      (node (ref "U2") (pin "22") (pinfunction "22_22") (pintype "passive"))
      (node (ref "U2") (pin "24") (pinfunction "24_24") (pintype "passive"))
      (node (ref "U2") (pin "26") (pinfunction "26_26") (pintype "passive"))
      (node (ref "U2") (pin "28") (pinfunction "28_28") (pintype "passive"))
      (node (ref "U2") (pin "30") (pinfunction "30_30") (pintype "passive"))
      (node (ref "U2") (pin "32") (pinfunction "32_32") (pintype "passive"))
      (node (ref "U2") (pin "4") (pinfunction "4_4") (pintype "passive"))
      (node (ref "U2") (pin "6") (pinfunction "6_6") (pintype "passive"))
      (node (ref "U2") (pin "8") (pinfunction "8_8") (pintype "passive"))
      (node (ref "U20") (pin "4") (pinfunction "GND_4") (pintype "passive"))
      (node (ref "U21") (pin "15") (pinfunction "REF_IN(-)_15") (pintype "passive"))
      (node (ref "U21") (pin "24") (pinfunction "DGND_24") (pintype "passive"))
      (node (ref "U21") (pin "4") (pinfunction "POL_4") (pintype "passive"))
      (node (ref "U21") (pin "8") (pinfunction "AGND_8") (pintype "passive"))
      (node (ref "U23") (pin "15") (pinfunction "REF_IN(-)_15") (pintype "passive"))
      (node (ref "U23") (pin "24") (pinfunction "DGND_24") (pintype "passive"))
      (node (ref "U23") (pin "4") (pinfunction "POL_4") (pintype "passive"))
      (node (ref "U23") (pin "8") (pinfunction "AGND_8") (pintype "passive"))
      (node (ref "U24") (pin "15") (pinfunction "REF_IN(-)_15") (pintype "passive"))
      (node (ref "U24") (pin "24") (pinfunction "DGND_24") (pintype "passive"))
      (node (ref "U24") (pin "4") (pinfunction "POL_4") (pintype "passive"))
      (node (ref "U24") (pin "8") (pinfunction "AGND_8") (pintype "passive"))
      (node (ref "U25") (pin "15") (pinfunction "REF_IN(-)_15") (pintype "passive"))
      (node (ref "U25") (pin "24") (pinfunction "DGND_24") (pintype "passive"))
      (node (ref "U25") (pin "4") (pinfunction "POL_4") (pintype "passive"))
      (node (ref "U25") (pin "8") (pinfunction "AGND_8") (pintype "passive"))
      (node (ref "U26") (pin "15") (pinfunction "REF_IN(-)_15") (pintype "passive"))
      (node (ref "U26") (pin "24") (pinfunction "DGND_24") (pintype "passive"))
      (node (ref "U26") (pin "4") (pinfunction "POL_4") (pintype "passive"))
      (node (ref "U26") (pin "8") (pinfunction "AGND_8") (pintype "passive"))
      (node (ref "U27") (pin "15") (pinfunction "REF_IN(-)_15") (pintype "passive"))
      (node (ref "U27") (pin "24") (pinfunction "DGND_24") (pintype "passive"))
      (node (ref "U27") (pin "4") (pinfunction "POL_4") (pintype "passive"))
      (node (ref "U27") (pin "8") (pinfunction "AGND_8") (pintype "passive"))
      (node (ref "U28") (pin "15") (pinfunction "REF_IN(-)_15") (pintype "passive"))
      (node (ref "U28") (pin "24") (pinfunction "DGND_24") (pintype "passive"))
      (node (ref "U28") (pin "4") (pinfunction "POL_4") (pintype "passive"))
      (node (ref "U28") (pin "8") (pinfunction "AGND_8") (pintype "passive"))
      (node (ref "U4") (pin "4") (pinfunction "GND_4") (pintype "passive"))
      (node (ref "U5") (pin "1") (pinfunction "V4BGND_1") (pintype "passive"))
      (node (ref "U5") (pin "10") (pinfunction "V7BGND_10") (pintype "passive"))
      (node (ref "U5") (pin "11") (pinfunction "V7AGND_11") (pintype "passive"))
      (node (ref "U5") (pin "13") (pinfunction "V6AGND_13") (pintype "passive"))
      (node (ref "U5") (pin "16") (pinfunction "AGND_4_16") (pintype "passive"))
      (node (ref "U5") (pin "18") (pinfunction "V5AGND_18") (pintype "passive"))
      (node (ref "U5") (pin "20") (pinfunction "V4AGND_20") (pintype "passive"))
      (node (ref "U5") (pin "21") (pinfunction "V3AGND_21") (pintype "passive"))
      (node (ref "U5") (pin "23") (pinfunction "V2AGND_23") (pintype "passive"))
      (node (ref "U5") (pin "25") (pinfunction "V1AGND_25") (pintype "passive"))
      (node (ref "U5") (pin "27") (pinfunction "V0AGND_27") (pintype "passive"))
      (node (ref "U5") (pin "29") (pinfunction "AGND_29") (pintype "passive"))
      (node (ref "U5") (pin "3") (pinfunction "V5BGND_3") (pintype "passive"))
      (node (ref "U5") (pin "32") (pinfunction "REFGND_32") (pintype "passive"))
      (node (ref "U5") (pin "34") (pinfunction "REFINOUTGND_34") (pintype "passive"))
      (node (ref "U5") (pin "35") (pinfunction "REFSEL_35") (pintype "passive"))
      (node (ref "U5") (pin "37") (pinfunction "SEQEN_37") (pintype "passive"))
      (node (ref "U5") (pin "38") (pinfunction "HW_RNGSEL1_38") (pintype "passive"))
      (node (ref "U5") (pin "39") (pinfunction "HW_RNGSEL0_39") (pintype "passive"))
      (node (ref "U5") (pin "41") (pinfunction "DB0_41") (pintype "passive"))
      (node (ref "U5") (pin "42") (pinfunction "DB1_42") (pintype "passive"))
      (node (ref "U5") (pin "43") (pinfunction "DB2_43") (pintype "passive"))
      (node (ref "U5") (pin "44") (pinfunction "DB3_44") (pintype "passive"))
      (node (ref "U5") (pin "45") (pinfunction "DB4/*SER1W_45") (pintype "passive"))
      (node (ref "U5") (pin "46") (pinfunction "DB5/CRCEN_46") (pintype "passive"))
      (node (ref "U5") (pin "47") (pinfunction "DB6_47") (pintype "passive"))
      (node (ref "U5") (pin "48") (pinfunction "DB7_48") (pintype "passive"))
      (node (ref "U5") (pin "5") (pinfunction "AGND_2_5") (pintype "passive"))
      (node (ref "U5") (pin "50") (pinfunction "DGND_50") (pintype "passive"))
      (node (ref "U5") (pin "51") (pinfunction "REGGNDD_51") (pintype "passive"))
      (node (ref "U5") (pin "53") (pinfunction "DB8_53") (pintype "passive"))
      (node (ref "U5") (pin "54") (pinfunction "DB9_54") (pintype "passive"))
      (node (ref "U5") (pin "58") (pinfunction "DB13/OS0_58") (pintype "passive"))
      (node (ref "U5") (pin "59") (pinfunction "DB14/OS1_59") (pintype "passive"))
      (node (ref "U5") (pin "60") (pinfunction "DB15/OS2_60") (pintype "passive"))
      (node (ref "U5") (pin "61") (pinfunction "*WR/BURST_61") (pintype "passive"))
      (node (ref "U5") (pin "64") (pinfunction "CHSEL0_64") (pintype "passive"))
      (node (ref "U5") (pin "65") (pinfunction "CHSEL1_65") (pintype "passive"))
      (node (ref "U5") (pin "66") (pinfunction "CHSEL2_66") (pintype "passive"))
      (node (ref "U5") (pin "69") (pinfunction "REGGND_69") (pintype "passive"))
      (node (ref "U5") (pin "72") (pinfunction "AGND_3_72") (pintype "passive"))
      (node (ref "U5") (pin "74") (pinfunction "V0BGND_74") (pintype "passive"))
      (node (ref "U5") (pin "76") (pinfunction "V1BGND_76") (pintype "passive"))
      (node (ref "U5") (pin "78") (pinfunction "V2BGND_78") (pintype "passive"))
      (node (ref "U5") (pin "8") (pinfunction "V6BGND_8") (pintype "passive"))
      (node (ref "U5") (pin "80") (pinfunction "V3BGND_80") (pintype "passive"))
      (node (ref "X1") (pin "3") (pinfunction "S_3") (pintype "passive"))
      (node (ref "Y1") (pin "2") (pinfunction "GND_2") (pintype "bidirectional"))
      (node (ref "Y3") (pin "2") (pinfunction "GND_2") (pintype "bidirectional"))
    )
    (net (code "100") (name "HB_CURR_LIM") (class "Default")
      (node (ref "LED1") (pin "A") (pinfunction "A_A") (pintype "passive"))
      (node (ref "R11") (pin "1") (pinfunction "1_1") (pintype "passive"))
    )
    (net (code "101") (name "HEARTBEAT") (class "Default")
      (node (ref "R11") (pin "2") (pinfunction "2_2") (pintype "passive"))
      (node (ref "SV1") (pin "3") (pinfunction "3_3") (pintype "passive"))
      (node (ref "U$1") (pin "6-OUT1D") (pinfunction "6-OUT1D_6-OUT1D") (pintype "bidirectional"))
    )
    (net (code "102") (name "LC_1_CS0") (class "Default")
      (node (ref "SV1") (pin "29") (pinfunction "29_29") (pintype "passive"))
      (node (ref "U$1") (pin "41-A17/MISO1") (pinfunction "41-A17/MISO1_41-A17/MISO1") (pintype "bidirectional"))
      (node (ref "U18") (pin "19") (pinfunction "*CS_19") (pintype "passive"))
    )
    (net (code "103") (name "LC_1_CS1") (class "Default")
      (node (ref "SV1") (pin "26") (pinfunction "26_26") (pintype "passive"))
      (node (ref "U$1") (pin "14-A0/TX3/SPDIF_OUT") (pinfunction "14-A0/TX3/SPDIF_OUT_14-A0/TX3/SPDIF_OUT") (pintype "bidirectional"))
      (node (ref "U21") (pin "19") (pinfunction "*CS_19") (pintype "passive"))
    )
    (net (code "104") (name "LC_1_CS2") (class "Default")
      (node (ref "SV1") (pin "24") (pinfunction "24_24") (pintype "passive"))
      (node (ref "U$1") (pin "15-A1/RX3/SPDIF_IN") (pinfunction "15-A1/RX3/SPDIF_IN_15-A1/RX3/SPDIF_IN") (pintype "bidirectional"))
      (node (ref "U23") (pin "19") (pinfunction "*CS_19") (pintype "passive"))
    )
    (net (code "105") (name "LC_1_CS3") (class "Default")
      (node (ref "SV1") (pin "22") (pinfunction "22_22") (pintype "passive"))
      (node (ref "U$1") (pin "16-A2/RX4/SCL1") (pinfunction "16-A2/RX4/SCL1_16-A2/RX4/SCL1") (pintype "bidirectional"))
      (node (ref "U24") (pin "19") (pinfunction "*CS_19") (pintype "passive"))
    )
    (net (code "106") (name "LC_1_CS4") (class "Default")
      (node (ref "SV1") (pin "40") (pinfunction "40_40") (pintype "passive"))
      (node (ref "U$1") (pin "33-MCLK2") (pinfunction "33-MCLK2_33-MCLK2") (pintype "bidirectional"))
      (node (ref "U25") (pin "19") (pinfunction "*CS_19") (pintype "passive"))
    )
    (net (code "107") (name "LC_1_CS5") (class "Default")
      (node (ref "SV1") (pin "38") (pinfunction "38_38") (pintype "passive"))
      (node (ref "U$1") (pin "34-RX8") (pinfunction "34-RX8_34-RX8") (pintype "bidirectional"))
      (node (ref "U26") (pin "19") (pinfunction "*CS_19") (pintype "passive"))
    )
    (net (code "108") (name "LC_1_CS6") (class "Default")
      (node (ref "SV1") (pin "37") (pinfunction "37_37") (pintype "passive"))
      (node (ref "U$1") (pin "35-TX8") (pinfunction "35/TX8_35-TX8") (pintype "bidirectional"))
      (node (ref "U27") (pin "19") (pinfunction "*CS_19") (pintype "passive"))
    )
    (net (code "109") (name "LC_1_CS7") (class "Default")
      (node (ref "SV1") (pin "36") (pinfunction "36_36") (pintype "passive"))
      (node (ref "U$1") (pin "36-PWM") (pinfunction "36-PWM_36-PWM") (pintype "bidirectional"))
      (node (ref "U28") (pin "19") (pinfunction "*CS_19") (pintype "passive"))
    )
    (net (code "110") (name "LC_1_MCLK") (class "Default")
      (node (ref "U18") (pin "2") (pinfunction "MCLK_IN_2") (pintype "passive"))
      (node (ref "Y3") (pin "3") (pinfunction "OUT_3") (pintype "bidirectional"))
    )
    (net (code "111") (name "LC_1_RDY0") (class "Default")
      (node (ref "SV1") (pin "13") (pinfunction "13_13") (pintype "passive"))
      (node (ref "U$1") (pin "20-A6/TX5/LRCLK1") (pinfunction "20-A6/TX5/LRCLK1_20-A6/TX5/LRCLK1") (pintype "bidirectional"))
      (node (ref "U18") (pin "20") (pinfunction "*RDY_20") (pintype "passive"))
    )
    (net (code "112") (name "LC_1_RDY1") (class "Default")
      (node (ref "SV1") (pin "15") (pinfunction "15_15") (pintype "passive"))
      (node (ref "U$1") (pin "19-A5/SCL0") (pinfunction "19-A5/SCL0_19-A5/SCL0") (pintype "bidirectional"))
      (node (ref "U21") (pin "20") (pinfunction "*RDY_20") (pintype "passive"))
    )
    (net (code "113") (name "LC_1_RDY2") (class "Default")
      (node (ref "SV1") (pin "16") (pinfunction "16_16") (pintype "passive"))
      (node (ref "U$1") (pin "18-A4/SDA0") (pinfunction "18-A4/SDA0_18-A4/SDA0") (pintype "bidirectional"))
      (node (ref "U23") (pin "20") (pinfunction "*RDY_20") (pintype "passive"))
    )
    (net (code "114") (name "LC_1_RDY3") (class "Default")
      (node (ref "SV1") (pin "18") (pinfunction "18_18") (pintype "passive"))
      (node (ref "U$1") (pin "17-A3/TX4/SDA1") (pinfunction "17-A3/TX4/SDA1_17-A3/TX4/SDA1") (pintype "bidirectional"))
      (node (ref "U24") (pin "20") (pinfunction "*RDY_20") (pintype "passive"))
    )
    (net (code "115") (name "LC_1_RDY4") (class "Default")
      (node (ref "SV1") (pin "31") (pinfunction "31_31") (pintype "passive"))
      (node (ref "U$1") (pin "40-A16/CS1") (pinfunction "40-A16/CS1_40-A16/CS1") (pintype "bidirectional"))
      (node (ref "U25") (pin "20") (pinfunction "*RDY_20") (pintype "passive"))
    )
    (net (code "116") (name "LC_1_RDY5") (class "Default")
      (node (ref "SV1") (pin "32") (pinfunction "32_32") (pintype "passive"))
      (node (ref "U$1") (pin "39-A15/CS/OUT1A") (pinfunction "39-A15/CS/OUT1A_39-A15/CS/OUT1A") (pintype "bidirectional"))
      (node (ref "U26") (pin "20") (pinfunction "*RDY_20") (pintype "passive"))
    )
    (net (code "117") (name "LC_1_RDY6") (class "Default")
      (node (ref "SV1") (pin "33") (pinfunction "33_33") (pintype "passive"))
      (node (ref "U$1") (pin "38-A14/CS/IN1") (pinfunction "38-A14/CS/IN1_38-A14/CS/IN1") (pintype "bidirectional"))
      (node (ref "U27") (pin "20") (pinfunction "*RDY_20") (pintype "passive"))
    )
    (net (code "118") (name "LC_1_RDY7") (class "Default")
      (node (ref "SV1") (pin "35") (pinfunction "35_35") (pintype "passive"))
      (node (ref "U$1") (pin "37-PWM") (pinfunction "37-PWM_37-PWM") (pintype "bidirectional"))
      (node (ref "U28") (pin "20") (pinfunction "*RDY_20") (pintype "passive"))
    )
    (net (code "119") (name "LDAC") (class "Default")
      (node (ref "SV1") (pin "11") (pinfunction "11_11") (pintype "passive"))
      (node (ref "U$1") (pin "4-BCLK2") (pinfunction "4-BCLK2_4-BCLK2") (pintype "bidirectional"))
      (node (ref "U19") (pin "1") (pinfunction "*LDAC_1") (pintype "passive"))
    )
    (net (code "120") (name "MISO") (class "Default")
      (node (ref "SV1") (pin "21") (pinfunction "21_21") (pintype "passive"))
      (node (ref "U$1") (pin "12-MISO/MQSL") (pinfunction "12-MISO/MQSL_12-MISO/MQSL") (pintype "bidirectional"))
      (node (ref "U18") (pin "21") (pinfunction "DOUT_21") (pintype "passive"))
      (node (ref "U19") (pin "49") (pinfunction "SDO_49") (pintype "passive"))
      (node (ref "U21") (pin "21") (pinfunction "DOUT_21") (pintype "passive"))
      (node (ref "U23") (pin "21") (pinfunction "DOUT_21") (pintype "passive"))
      (node (ref "U24") (pin "21") (pinfunction "DOUT_21") (pintype "passive"))
      (node (ref "U25") (pin "21") (pinfunction "DOUT_21") (pintype "passive"))
      (node (ref "U26") (pin "21") (pinfunction "DOUT_21") (pintype "passive"))
      (node (ref "U27") (pin "21") (pinfunction "DOUT_21") (pintype "passive"))
      (node (ref "U28") (pin "21") (pinfunction "DOUT_21") (pintype "passive"))
      (node (ref "U5") (pin "57") (pinfunction "DB12/SDOA_57") (pintype "passive"))
    )
    (net (code "121") (name "MOSI") (class "Default")
      (node (ref "SV1") (pin "19") (pinfunction "19_19") (pintype "passive"))
      (node (ref "U$1") (pin "11-MOSI/CTX1") (pinfunction "11-MOSI/CTX1_11-MOSI/CTX1") (pintype "bidirectional"))
      (node (ref "U18") (pin "22") (pinfunction "DIN_22") (pintype "passive"))
      (node (ref "U19") (pin "47") (pinfunction "SDI_47") (pintype "passive"))
      (node (ref "U21") (pin "22") (pinfunction "DIN_22") (pintype "passive"))
      (node (ref "U23") (pin "22") (pinfunction "DIN_22") (pintype "passive"))
      (node (ref "U24") (pin "22") (pinfunction "DIN_22") (pintype "passive"))
      (node (ref "U25") (pin "22") (pinfunction "DIN_22") (pintype "passive"))
      (node (ref "U26") (pin "22") (pinfunction "DIN_22") (pintype "passive"))
      (node (ref "U27") (pin "22") (pinfunction "DIN_22") (pintype "passive"))
      (node (ref "U28") (pin "22") (pinfunction "DIN_22") (pintype "passive"))
      (node (ref "U5") (pin "55") (pinfunction "DB10/SDI_55") (pintype "passive"))
    )
    (net (code "122") (name "N$12") (class "Default")
      (node (ref "SV1") (pin "28") (pinfunction "28_28") (pintype "passive"))
    )
    (net (code "123") (name "N$13") (class "Default")
      (node (ref "SV1") (pin "27") (pinfunction "27_27") (pintype "passive"))
    )
    (net (code "124") (name "PG_CURR_LIM") (class "Default")
      (node (ref "LED4") (pin "A") (pinfunction "A_A") (pintype "passive"))
      (node (ref "R1") (pin "1") (pinfunction "1_1") (pintype "passive"))
    )
    (net (code "125") (name "PG_SIG") (class "Default")
      (node (ref "Q1") (pin "B") (pinfunction "B_B") (pintype "passive"))
      (node (ref "R12") (pin "1") (pinfunction "1_1") (pintype "passive"))
    )
    (net (code "126") (name "POWER_GOOD") (class "Default")
      (node (ref "PL1") (pin "8") (pinfunction "S_8") (pintype "passive"))
      (node (ref "R12") (pin "2") (pinfunction "2_2") (pintype "passive"))
    )
    (net (code "127") (name "POWER_GOOD_SUPP") (class "Default")
      (node (ref "Q1") (pin "E") (pinfunction "E_E") (pintype "passive"))
      (node (ref "R1") (pin "2") (pinfunction "2_2") (pintype "passive"))
    )
    (net (code "128") (name "PSU_ENABLE") (class "Default")
      (node (ref "PL1") (pin "16") (pinfunction "S_16") (pintype "passive"))
      (node (ref "S1") (pin "2") (pinfunction "2_2") (pintype "passive"))
    )
    (net (code "129") (name "PWR") (class "Default")
      (node (ref "C15") (pin "+") (pinfunction "+_+") (pintype "passive"))
      (node (ref "JP9") (pin "1") (pinfunction "1_1") (pintype "passive"))
      (node (ref "SV1") (pin "2") (pinfunction "2_2") (pintype "passive"))
      (node (ref "SV1") (pin "4") (pinfunction "4_4") (pintype "passive"))
      (node (ref "U$1") (pin "VIN") (pinfunction "VIN_VIN") (pintype "bidirectional"))
    )
    (net (code "130") (name "RX") (class "Default")
      (node (ref "JP8") (pin "2") (pinfunction "2_2") (pintype "passive"))
      (node (ref "SV1") (pin "10") (pinfunction "10_10") (pintype "passive"))
      (node (ref "U$1") (pin "0-RX1/CS1/CRX2") (pinfunction "0-RX1/CS1/CRX2_0-RX1/CS1/CRX2") (pintype "bidirectional"))
    )
    (net (code "131") (name "SCLK") (class "Default")
      (node (ref "SV1") (pin "23") (pinfunction "23_23") (pintype "passive"))
      (node (ref "U$1") (pin "13-SCK/LED") (pinfunction "13-SCK/LED_13-SCK/LED") (pintype "bidirectional"))
      (node (ref "U18") (pin "1") (pinfunction "SCLK_1") (pintype "passive"))
      (node (ref "U19") (pin "46") (pinfunction "SCLK_46") (pintype "passive"))
      (node (ref "U21") (pin "1") (pinfunction "SCLK_1") (pintype "passive"))
      (node (ref "U23") (pin "1") (pinfunction "SCLK_1") (pintype "passive"))
      (node (ref "U24") (pin "1") (pinfunction "SCLK_1") (pintype "passive"))
      (node (ref "U25") (pin "1") (pinfunction "SCLK_1") (pintype "passive"))
      (node (ref "U26") (pin "1") (pinfunction "SCLK_1") (pintype "passive"))
      (node (ref "U27") (pin "1") (pinfunction "SCLK_1") (pintype "passive"))
      (node (ref "U28") (pin "1") (pinfunction "SCLK_1") (pintype "passive"))
      (node (ref "U5") (pin "62") (pinfunction "SCLK/*RD_62") (pintype "passive"))
    )
    (net (code "132") (name "SS_ADC_2") (class "Default")
      (node (ref "SV1") (pin "7") (pinfunction "7_7") (pintype "passive"))
      (node (ref "U$1") (pin "3-LRCLK2") (pinfunction "3-LRCLK2_3-LRCLK2") (pintype "bidirectional"))
      (node (ref "U5") (pin "63") (pinfunction "*CS_63") (pintype "passive"))
    )
    (net (code "133") (name "SS_DAC_2") (class "Default")
      (node (ref "SV1") (pin "12") (pinfunction "12_12") (pintype "passive"))
      (node (ref "U$1") (pin "5-IN2") (pinfunction "5-IN2_5-IN2") (pintype "bidirectional"))
      (node (ref "U19") (pin "45") (pinfunction "*SYNC_45") (pintype "passive"))
    )
    (net (code "134") (name "TX") (class "Default")
      (node (ref "JP8") (pin "1") (pinfunction "1_1") (pintype "passive"))
      (node (ref "SV1") (pin "8") (pinfunction "8_8") (pintype "passive"))
      (node (ref "U$1") (pin "1-TX1/MISO1/CTX2") (pinfunction "1-TX1/MISO1/CTX2_1-TX1/MISO1/CTX2") (pintype "bidirectional"))
    )
    (net (code "135") (name "VDD") (class "Default")
      (node (ref "C12") (pin "+") (pinfunction "+_+") (pintype "passive"))
      (node (ref "C141") (pin "1") (pinfunction "1_1") (pintype "passive"))
      (node (ref "C143") (pin "1") (pinfunction "1_1") (pintype "passive"))
      (node (ref "C148") (pin "1") (pinfunction "1_1") (pintype "passive"))
      (node (ref "C23") (pin "+") (pinfunction "+_+") (pintype "passive"))
      (node (ref "C24") (pin "+") (pinfunction "+_+") (pintype "passive"))
      (node (ref "C27") (pin "+") (pinfunction "+_+") (pintype "passive"))
      (node (ref "C33") (pin "1") (pinfunction "1_1") (pintype "passive"))
      (node (ref "C8") (pin "+") (pinfunction "+_+") (pintype "passive"))
      (node (ref "C9") (pin "+") (pinfunction "+_+") (pintype "passive"))
      (node (ref "J17") (pin "1") (pinfunction "1_1") (pintype "input"))
      (node (ref "J18") (pin "1") (pinfunction "1_1") (pintype "input"))
      (node (ref "J19") (pin "1") (pinfunction "1_1") (pintype "input"))
      (node (ref "J20") (pin "1") (pinfunction "1_1") (pintype "input"))
      (node (ref "J21") (pin "1") (pinfunction "1_1") (pintype "input"))
      (node (ref "J22") (pin "1") (pinfunction "1_1") (pintype "input"))
      (node (ref "J23") (pin "1") (pinfunction "1_1") (pintype "input"))
      (node (ref "J24") (pin "1") (pinfunction "1_1") (pintype "input"))
      (node (ref "J25") (pin "1") (pinfunction "1_1") (pintype "input"))
      (node (ref "J26") (pin "1") (pinfunction "1_1") (pintype "input"))
      (node (ref "J27") (pin "1") (pinfunction "1_1") (pintype "input"))
      (node (ref "J28") (pin "1") (pinfunction "1_1") (pintype "input"))
      (node (ref "J29") (pin "1") (pinfunction "1_1") (pintype "input"))
      (node (ref "J30") (pin "1") (pinfunction "1_1") (pintype "input"))
      (node (ref "J31") (pin "1") (pinfunction "1_1") (pintype "input"))
      (node (ref "J32") (pin "1") (pinfunction "1_1") (pintype "input"))
      (node (ref "PL1") (pin "11") (pinfunction "S_11") (pintype "passive"))
      (node (ref "R10") (pin "2") (pinfunction "2_2") (pintype "passive"))
      (node (ref "U19") (pin "11") (pinfunction "VDD_11") (pintype "passive"))
      (node (ref "U19") (pin "28") (pinfunction "VDD_2_28") (pintype "passive"))
      (node (ref "U20") (pin "2") (pinfunction "VIN_2") (pintype "passive"))
      (node (ref "U4") (pin "2") (pinfunction "VIN_2") (pintype "passive"))
      (node (ref "X1") (pin "2") (pinfunction "S_2") (pintype "passive"))
    )
    (net (code "136") (name "VDD_CURR_LIM") (class "Default")
      (node (ref "LED5") (pin "A") (pinfunction "A_A") (pintype "passive"))
      (node (ref "R10") (pin "1") (pinfunction "1_1") (pintype "passive"))
    )
    (net (code "137") (name "VREF_2") (class "Default")
      (node (ref "C10") (pin "+") (pinfunction "+_+") (pintype "passive"))
      (node (ref "C150") (pin "1") (pinfunction "1_1") (pintype "passive"))
      (node (ref "C151") (pin "1") (pinfunction "1_1") (pintype "passive"))
      (node (ref "U19") (pin "13") (pinfunction "VREF1_13") (pintype "passive"))
      (node (ref "U19") (pin "31") (pinfunction "VREF0_31") (pintype "passive"))
      (node (ref "U20") (pin "6") (pinfunction "VOUT_6") (pintype "passive"))
    )
    (net (code "138") (name "VSS") (class "Default")
      (node (ref "C145") (pin "1") (pinfunction "1_1") (pintype "passive"))
      (node (ref "C147") (pin "1") (pinfunction "1_1") (pintype "passive"))
      (node (ref "C16") (pin "-") (pinfunction "-_-") (pintype "passive"))
      (node (ref "C25") (pin "-") (pinfunction "-_-") (pintype "passive"))
      (node (ref "C26") (pin "-") (pinfunction "-_-") (pintype "passive"))
      (node (ref "PL1") (pin "14") (pinfunction "S_14") (pintype "passive"))
      (node (ref "U19") (pin "12") (pinfunction "VSS_2_12") (pintype "passive"))
      (node (ref "U19") (pin "29") (pinfunction "VSS_29") (pintype "passive"))
    )
    (net (code "139") (name "unconnected-(PL1A-S-Pad1)") (class "Default")
      (node (ref "PL1") (pin "1") (pinfunction "S_1") (pintype "passive"))
    )
    (net (code "140") (name "unconnected-(PL1B-S-Pad10)") (class "Default")
      (node (ref "PL1") (pin "10") (pinfunction "S_10") (pintype "passive"))
    )
    (net (code "141") (name "unconnected-(PL1D-S-Pad12)") (class "Default")
      (node (ref "PL1") (pin "12") (pinfunction "S_12") (pintype "passive"))
    )
    (net (code "142") (name "unconnected-(PL1E-S-Pad13)") (class "Default")
      (node (ref "PL1") (pin "13") (pinfunction "S_13") (pintype "passive"))
    )
    (net (code "143") (name "unconnected-(PL1M-S-Pad20)") (class "Default")
      (node (ref "PL1") (pin "20") (pinfunction "S_20") (pintype "passive"))
    )
    (net (code "144") (name "unconnected-(PL1N-S-Pad21)") (class "Default")
      (node (ref "PL1") (pin "21") (pinfunction "S_21") (pintype "passive"))
    )
    (net (code "145") (name "unconnected-(PL1O-S-Pad22)") (class "Default")
      (node (ref "PL1") (pin "22") (pinfunction "S_22") (pintype "passive"))
    )
    (net (code "146") (name "unconnected-(PL1S-S-Pad4)") (class "Default")
      (node (ref "PL1") (pin "4") (pinfunction "S_4") (pintype "passive"))
    )
    (net (code "147") (name "unconnected-(PL1U-S-Pad6)") (class "Default")
      (node (ref "PL1") (pin "6") (pinfunction "S_6") (pintype "passive"))
    )
    (net (code "148") (name "unconnected-(PL1X-S-Pad9)") (class "Default")
      (node (ref "PL1") (pin "9") (pinfunction "S_9") (pintype "passive"))
    )
    (net (code "149") (name "unconnected-(S1-Pad1)") (class "Default")
      (node (ref "S1") (pin "1") (pinfunction "1_1") (pintype "passive"))
    )
    (net (code "150") (name "unconnected-(S2-S1-Pad2)") (class "Default")
      (node (ref "S2") (pin "2") (pinfunction "S1_2") (pintype "passive"))
    )
    (net (code "151") (name "unconnected-(S8-P-Pad3)") (class "Default")
      (node (ref "S8") (pin "3") (pinfunction "P_3") (pintype "passive"))
    )
    (net (code "152") (name "unconnected-(SV1-Pad1)") (class "Default")
      (node (ref "SV1") (pin "1") (pinfunction "1_1") (pintype "passive"))
    )
    (net (code "153") (name "unconnected-(U$1-5V-Pad+5V)") (class "Default")
      (node (ref "U$1") (pin "+5V") (pinfunction "5V_+5V") (pintype "bidirectional"))
    )
    (net (code "154") (name "unconnected-(U$1-Pad3V3-1)") (class "Default")
      (node (ref "U$1") (pin "3V3-1") (pinfunction "3V3-1_3V3-1") (pintype "bidirectional"))
    )
    (net (code "155") (name "unconnected-(U$1-Pad3V3-2)") (class "Default")
      (node (ref "U$1") (pin "3V3-2") (pinfunction "3V3-2_3V3-2") (pintype "bidirectional"))
    )
    (net (code "156") (name "unconnected-(U$1-Pad3V3-3)") (class "Default")
      (node (ref "U$1") (pin "3V3-3") (pinfunction "3V3-3_3V3-3") (pintype "bidirectional"))
    )
    (net (code "157") (name "unconnected-(U$1-Pad21-A7{slash}RX5{slash}BCLK1)") (class "Default")
      (node (ref "U$1") (pin "21-A7/RX5/BCLK1") (pinfunction "21-A7/RX5/BCLK1_21-A7/RX5/BCLK1") (pintype "bidirectional"))
    )
    (net (code "158") (name "unconnected-(U$1-Pad22-A8{slash}CTX1)") (class "Default")
      (node (ref "U$1") (pin "22-A8/CTX1") (pinfunction "22-A8/CTX1_22-A8/CTX1") (pintype "bidirectional"))
    )
    (net (code "159") (name "unconnected-(U$1-Pad23-A9{slash}CRX1{slash}MCLK1)") (class "Default")
      (node (ref "U$1") (pin "23-A9/CRX1/MCLK1") (pinfunction "23-A9/CRX1/MCLK1_23-A9/CRX1/MCLK1") (pintype "bidirectional"))
    )
    (net (code "160") (name "unconnected-(U$1-Pad24-A10{slash}TX6{slash}SCL2)") (class "Default")
      (node (ref "U$1") (pin "24-A10/TX6/SCL2") (pinfunction "24-A10/TX6/SCL2_24-A10/TX6/SCL2") (pintype "bidirectional"))
    )
    (net (code "161") (name "unconnected-(U$1-PadD+)") (class "Default")
      (node (ref "U$1") (pin "D+") (pinfunction "D+_D+") (pintype "bidirectional"))
    )
    (net (code "162") (name "unconnected-(U$1-PadD-)") (class "Default")
      (node (ref "U$1") (pin "D-") (pinfunction "D-_D-") (pintype "bidirectional"))
    )
    (net (code "163") (name "unconnected-(U$1-PadDM)") (class "Default")
      (node (ref "U$1") (pin "DM") (pinfunction "DM_DM") (pintype "bidirectional"))
    )
    (net (code "164") (name "unconnected-(U$1-PadDP)") (class "Default")
      (node (ref "U$1") (pin "DP") (pinfunction "DP_DP") (pintype "bidirectional"))
    )
    (net (code "165") (name "unconnected-(U$1-PadG)") (class "Default")
      (node (ref "U$1") (pin "G") (pinfunction "G_G") (pintype "bidirectional"))
    )
    (net (code "166") (name "unconnected-(U$1-PadGND2)") (class "Default")
      (node (ref "U$1") (pin "GND2") (pinfunction "GND2_GND2") (pintype "bidirectional"))
    )
    (net (code "167") (name "unconnected-(U$1-PadGND4)") (class "Default")
      (node (ref "U$1") (pin "GND4") (pinfunction "GND4_GND4") (pintype "bidirectional"))
    )
    (net (code "168") (name "unconnected-(U$1-PadGND5)") (class "Default")
      (node (ref "U$1") (pin "GND5") (pinfunction "GND5_GND5") (pintype "bidirectional"))
    )
    (net (code "169") (name "unconnected-(U$1-PadLED)") (class "Default")
      (node (ref "U$1") (pin "LED") (pinfunction "LED_LED") (pintype "bidirectional"))
    )
    (net (code "170") (name "unconnected-(U$1-PadON{slash}OFF)") (class "Default")
      (node (ref "U$1") (pin "ON/OFF") (pinfunction "ON/OFF_ON/OFF") (pintype "bidirectional"))
    )
    (net (code "171") (name "unconnected-(U$1-PadPROGRAM)") (class "Default")
      (node (ref "U$1") (pin "PROGRAM") (pinfunction "PROGRAM_PROGRAM") (pintype "bidirectional"))
    )
    (net (code "172") (name "unconnected-(U$1-PadR+)") (class "Default")
      (node (ref "U$1") (pin "R+") (pinfunction "R+_R+") (pintype "bidirectional"))
    )
    (net (code "173") (name "unconnected-(U$1-PadR-)") (class "Default")
      (node (ref "U$1") (pin "R-") (pinfunction "R-_R-") (pintype "bidirectional"))
    )
    (net (code "174") (name "unconnected-(U$1-PadT+)") (class "Default")
      (node (ref "U$1") (pin "T+") (pinfunction "T+_T+") (pintype "bidirectional"))
    )
    (net (code "175") (name "unconnected-(U$1-PadT-)") (class "Default")
      (node (ref "U$1") (pin "T-") (pinfunction "T-_T-") (pintype "bidirectional"))
    )
    (net (code "176") (name "unconnected-(U$1-PadVBAT)") (class "Default")
      (node (ref "U$1") (pin "VBAT") (pinfunction "VBAT_VBAT") (pintype "bidirectional"))
    )
    (net (code "177") (name "unconnected-(U$1-PadVUSB)") (class "Default")
      (node (ref "U$1") (pin "VUSB") (pinfunction "VUSB_VUSB") (pintype "bidirectional"))
    )
    (net (code "178") (name "unconnected-(U2-Pad33)") (class "Default")
      (node (ref "U2") (pin "33") (pinfunction "33_33") (pintype "passive"))
    )
    (net (code "179") (name "unconnected-(U2-Pad34)") (class "Default")
      (node (ref "U2") (pin "34") (pinfunction "34_34") (pintype "passive"))
    )
    (net (code "180") (name "unconnected-(U4-NIC-Pad7)") (class "Default")
      (node (ref "U4") (pin "7") (pinfunction "NIC_7") (pintype "passive"))
    )
    (net (code "181") (name "unconnected-(U4-NIC_2-Pad3)") (class "Default")
      (node (ref "U4") (pin "3") (pinfunction "NIC_2_3") (pintype "passive"))
    )
    (net (code "182") (name "unconnected-(U4-TP-Pad8)") (class "Default")
      (node (ref "U4") (pin "8") (pinfunction "TP_8") (pintype "passive"))
    )
    (net (code "183") (name "unconnected-(U4-TP_2-Pad1)") (class "Default")
      (node (ref "U4") (pin "1") (pinfunction "TP_2_1") (pintype "passive"))
    )
    (net (code "184") (name "unconnected-(U4-TRIM-Pad5)") (class "Default")
      (node (ref "U4") (pin "5") (pinfunction "TRIM_5") (pintype "passive"))
    )
    (net (code "185") (name "unconnected-(U5-BUSY-Pad67)") (class "Default")
      (node (ref "U5") (pin "67") (pinfunction "BUSY_67") (pintype "passive"))
    )
    (net (code "186") (name "unconnected-(U5-DB11{slash}SDOB-Pad56)") (class "Default")
      (node (ref "U5") (pin "56") (pinfunction "DB11/SDOB_56") (pintype "passive"))
    )
    (net (code "187") (name "unconnected-(U18-*ACX-Pad17)") (class "Default")
      (node (ref "U18") (pin "17") (pinfunction "*ACX_17") (pintype "passive"))
    )
    (net (code "188") (name "unconnected-(U18-ACX-Pad16)") (class "Default")
      (node (ref "U18") (pin "16") (pinfunction "ACX_16") (pintype "passive"))
    )
    (net (code "189") (name "unconnected-(U18-VBIAS-Pad7)") (class "Default")
      (node (ref "U18") (pin "7") (pinfunction "VBIAS_7") (pintype "passive"))
    )
    (net (code "190") (name "unconnected-(U19-*BUSY-Pad5)") (class "Default")
      (node (ref "U19") (pin "5") (pinfunction "*BUSY_5") (pintype "passive"))
    )
    (net (code "191") (name "unconnected-(U19-*PEC-Pad48)") (class "Default")
      (node (ref "U19") (pin "48") (pinfunction "*PEC_48") (pintype "passive"))
    )
    (net (code "192") (name "unconnected-(U19-GPIO-Pad6)") (class "Default")
      (node (ref "U19") (pin "6") (pinfunction "GPIO_6") (pintype "passive"))
    )
    (net (code "193") (name "unconnected-(U19-MON_IN0-Pad8)") (class "Default")
      (node (ref "U19") (pin "8") (pinfunction "MON_IN0_8") (pintype "passive"))
    )
    (net (code "194") (name "unconnected-(U19-MON_IN1-Pad32)") (class "Default")
      (node (ref "U19") (pin "32") (pinfunction "MON_IN1_32") (pintype "passive"))
    )
    (net (code "195") (name "unconnected-(U19-MON_OUT-Pad7)") (class "Default")
      (node (ref "U19") (pin "7") (pinfunction "MON_OUT_7") (pintype "passive"))
    )
    (net (code "196") (name "unconnected-(U19-NC-Pad26)") (class "Default")
      (node (ref "U19") (pin "26") (pinfunction "NC_26") (pintype "passive"))
    )
    (net (code "197") (name "unconnected-(U19-NC_2-Pad27)") (class "Default")
      (node (ref "U19") (pin "27") (pinfunction "NC_2_27") (pintype "passive"))
    )
    (net (code "198") (name "unconnected-(U19-NC_3-Pad30)") (class "Default")
      (node (ref "U19") (pin "30") (pinfunction "NC_3_30") (pintype "passive"))
    )
    (net (code "199") (name "unconnected-(U19-NC_4-Pad9)") (class "Default")
      (node (ref "U19") (pin "9") (pinfunction "NC_4_9") (pintype "passive"))
    )
    (net (code "200") (name "unconnected-(U19-NC_5-Pad10)") (class "Default")
      (node (ref "U19") (pin "10") (pinfunction "NC_5_10") (pintype "passive"))
    )
    (net (code "201") (name "unconnected-(U19-NC_6-Pad14)") (class "Default")
      (node (ref "U19") (pin "14") (pinfunction "NC_6_14") (pintype "passive"))
    )
    (net (code "202") (name "unconnected-(U19-NC_7-Pad24)") (class "Default")
      (node (ref "U19") (pin "24") (pinfunction "NC_7_24") (pintype "passive"))
    )
    (net (code "203") (name "unconnected-(U19-NC_8-Pad25)") (class "Default")
      (node (ref "U19") (pin "25") (pinfunction "NC_8_25") (pintype "passive"))
    )
    (net (code "204") (name "unconnected-(U19-TEMP_OUT-Pad33)") (class "Default")
      (node (ref "U19") (pin "33") (pinfunction "TEMP_OUT_33") (pintype "passive"))
    )
    (net (code "205") (name "unconnected-(U20-NIC-Pad7)") (class "Default")
      (node (ref "U20") (pin "7") (pinfunction "NIC_7") (pintype "passive"))
    )
    (net (code "206") (name "unconnected-(U20-NIC_2-Pad3)") (class "Default")
      (node (ref "U20") (pin "3") (pinfunction "NIC_2_3") (pintype "passive"))
    )
    (net (code "207") (name "unconnected-(U20-TP-Pad8)") (class "Default")
      (node (ref "U20") (pin "8") (pinfunction "TP_8") (pintype "passive"))
    )
    (net (code "208") (name "unconnected-(U20-TP_2-Pad1)") (class "Default")
      (node (ref "U20") (pin "1") (pinfunction "TP_2_1") (pintype "passive"))
    )
    (net (code "209") (name "unconnected-(U20-TRIM-Pad5)") (class "Default")
      (node (ref "U20") (pin "5") (pinfunction "TRIM_5") (pintype "passive"))
    )
    (net (code "210") (name "unconnected-(U21-*ACX-Pad17)") (class "Default")
      (node (ref "U21") (pin "17") (pinfunction "*ACX_17") (pintype "passive"))
    )
    (net (code "211") (name "unconnected-(U21-ACX-Pad16)") (class "Default")
      (node (ref "U21") (pin "16") (pinfunction "ACX_16") (pintype "passive"))
    )
    (net (code "212") (name "unconnected-(U21-VBIAS-Pad7)") (class "Default")
      (node (ref "U21") (pin "7") (pinfunction "VBIAS_7") (pintype "passive"))
    )
    (net (code "213") (name "unconnected-(U23-*ACX-Pad17)") (class "Default")
      (node (ref "U23") (pin "17") (pinfunction "*ACX_17") (pintype "passive"))
    )
    (net (code "214") (name "unconnected-(U23-ACX-Pad16)") (class "Default")
      (node (ref "U23") (pin "16") (pinfunction "ACX_16") (pintype "passive"))
    )
    (net (code "215") (name "unconnected-(U23-VBIAS-Pad7)") (class "Default")
      (node (ref "U23") (pin "7") (pinfunction "VBIAS_7") (pintype "passive"))
    )
    (net (code "216") (name "unconnected-(U24-*ACX-Pad17)") (class "Default")
      (node (ref "U24") (pin "17") (pinfunction "*ACX_17") (pintype "passive"))
    )
    (net (code "217") (name "unconnected-(U24-ACX-Pad16)") (class "Default")
      (node (ref "U24") (pin "16") (pinfunction "ACX_16") (pintype "passive"))
    )
    (net (code "218") (name "unconnected-(U24-MCLK_OUT-Pad3)") (class "Default")
      (node (ref "U24") (pin "3") (pinfunction "MCLK_OUT_3") (pintype "passive"))
    )
    (net (code "219") (name "unconnected-(U24-VBIAS-Pad7)") (class "Default")
      (node (ref "U24") (pin "7") (pinfunction "VBIAS_7") (pintype "passive"))
    )
    (net (code "220") (name "unconnected-(U25-*ACX-Pad17)") (class "Default")
      (node (ref "U25") (pin "17") (pinfunction "*ACX_17") (pintype "passive"))
    )
    (net (code "221") (name "unconnected-(U25-ACX-Pad16)") (class "Default")
      (node (ref "U25") (pin "16") (pinfunction "ACX_16") (pintype "passive"))
    )
    (net (code "222") (name "unconnected-(U25-VBIAS-Pad7)") (class "Default")
      (node (ref "U25") (pin "7") (pinfunction "VBIAS_7") (pintype "passive"))
    )
    (net (code "223") (name "unconnected-(U26-*ACX-Pad17)") (class "Default")
      (node (ref "U26") (pin "17") (pinfunction "*ACX_17") (pintype "passive"))
    )
    (net (code "224") (name "unconnected-(U26-ACX-Pad16)") (class "Default")
      (node (ref "U26") (pin "16") (pinfunction "ACX_16") (pintype "passive"))
    )
    (net (code "225") (name "unconnected-(U26-VBIAS-Pad7)") (class "Default")
      (node (ref "U26") (pin "7") (pinfunction "VBIAS_7") (pintype "passive"))
    )
    (net (code "226") (name "unconnected-(U27-*ACX-Pad17)") (class "Default")
      (node (ref "U27") (pin "17") (pinfunction "*ACX_17") (pintype "passive"))
    )
    (net (code "227") (name "unconnected-(U27-ACX-Pad16)") (class "Default")
      (node (ref "U27") (pin "16") (pinfunction "ACX_16") (pintype "passive"))
    )
    (net (code "228") (name "unconnected-(U27-VBIAS-Pad7)") (class "Default")
      (node (ref "U27") (pin "7") (pinfunction "VBIAS_7") (pintype "passive"))
    )
    (net (code "229") (name "unconnected-(U28-*ACX-Pad17)") (class "Default")
      (node (ref "U28") (pin "17") (pinfunction "*ACX_17") (pintype "passive"))
    )
    (net (code "230") (name "unconnected-(U28-ACX-Pad16)") (class "Default")
      (node (ref "U28") (pin "16") (pinfunction "ACX_16") (pintype "passive"))
    )
    (net (code "231") (name "unconnected-(U28-MCLK_OUT-Pad3)") (class "Default")
      (node (ref "U28") (pin "3") (pinfunction "MCLK_OUT_3") (pintype "passive"))
    )
    (net (code "232") (name "unconnected-(U28-VBIAS-Pad7)") (class "Default")
      (node (ref "U28") (pin "7") (pinfunction "VBIAS_7") (pintype "passive"))
    )
    (net (code "233") (name "unconnected-(X1A-S-Pad1)") (class "Default")
      (node (ref "X1") (pin "1") (pinfunction "S_1") (pintype "passive"))
    )
    (net (code "234") (name "unconnected-(Y1-EN-Pad1)") (class "Default")
      (node (ref "Y1") (pin "1") (pinfunction "EN_1") (pintype "bidirectional"))
    )
    (net (code "235") (name "unconnected-(Y3-EN-Pad1)") (class "Default")
      (node (ref "Y3") (pin "1") (pinfunction "EN_1") (pintype "bidirectional"))
    )
  )
)
